# processor.net
KiCad netlist of a schematic drawn in Altium Designer
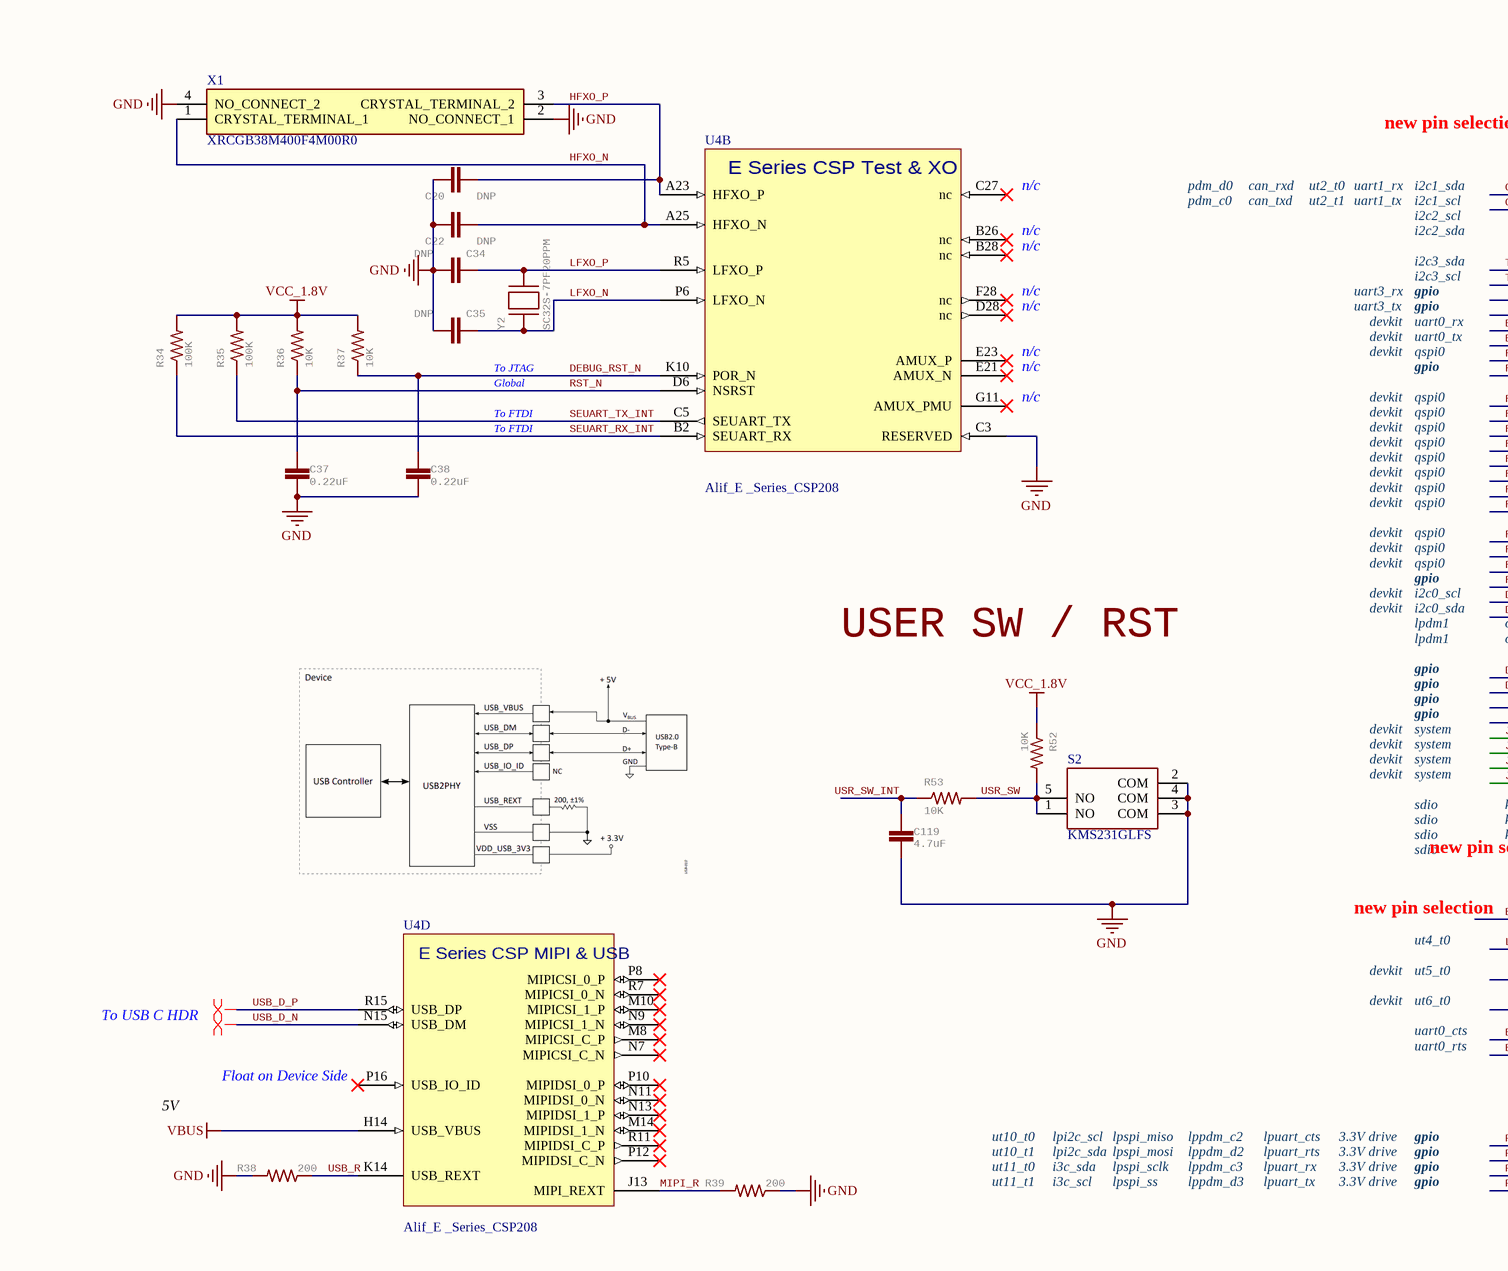
[diagram p0: processor.SchDoc, top left]
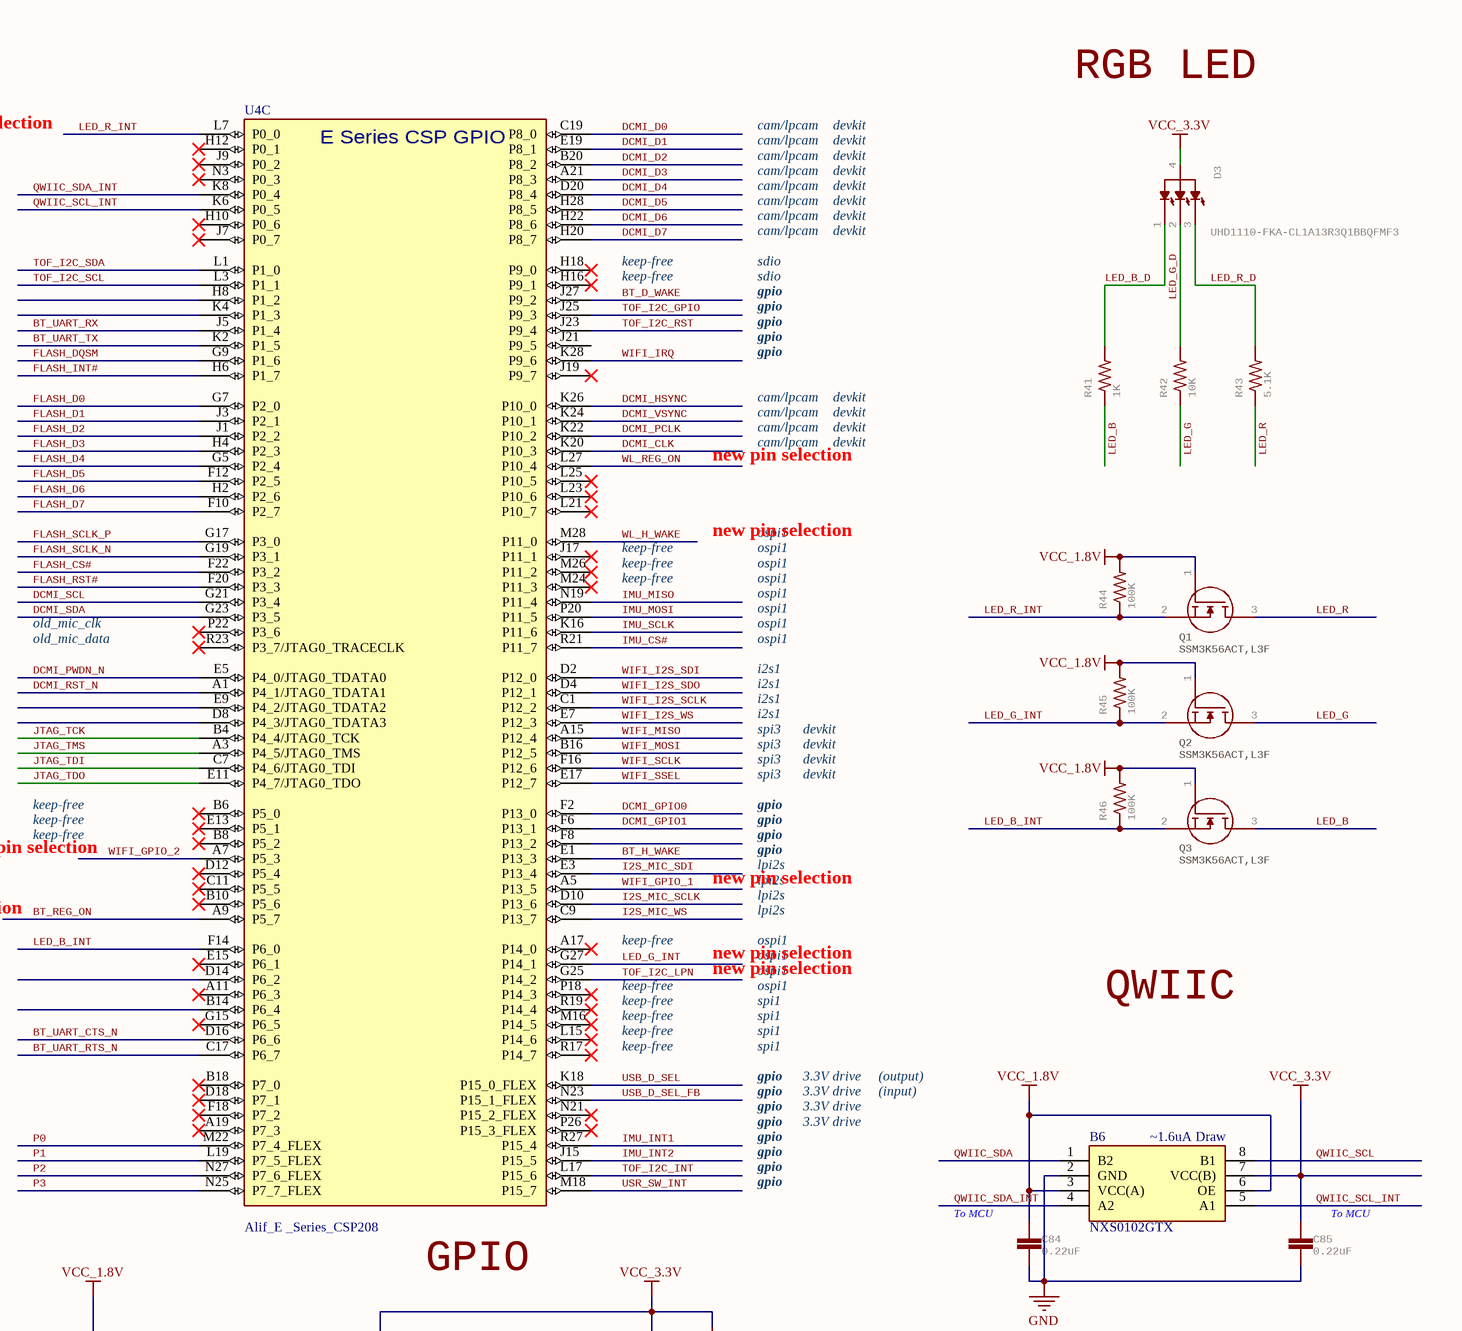
[diagram p1: processor.SchDoc, top right]
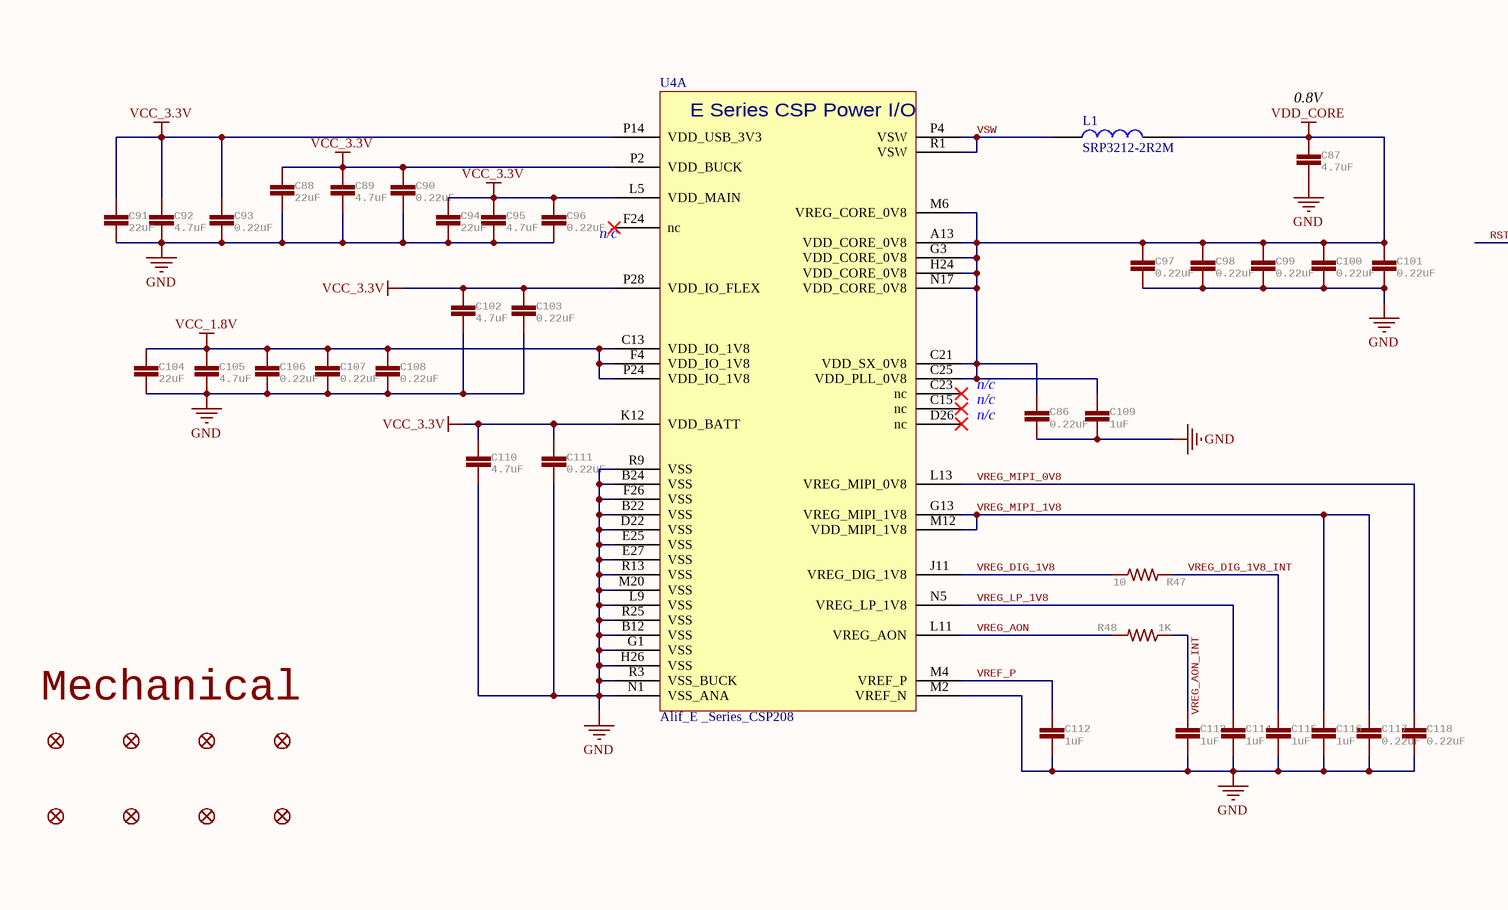
[diagram p2: processor.SchDoc, bottom left]
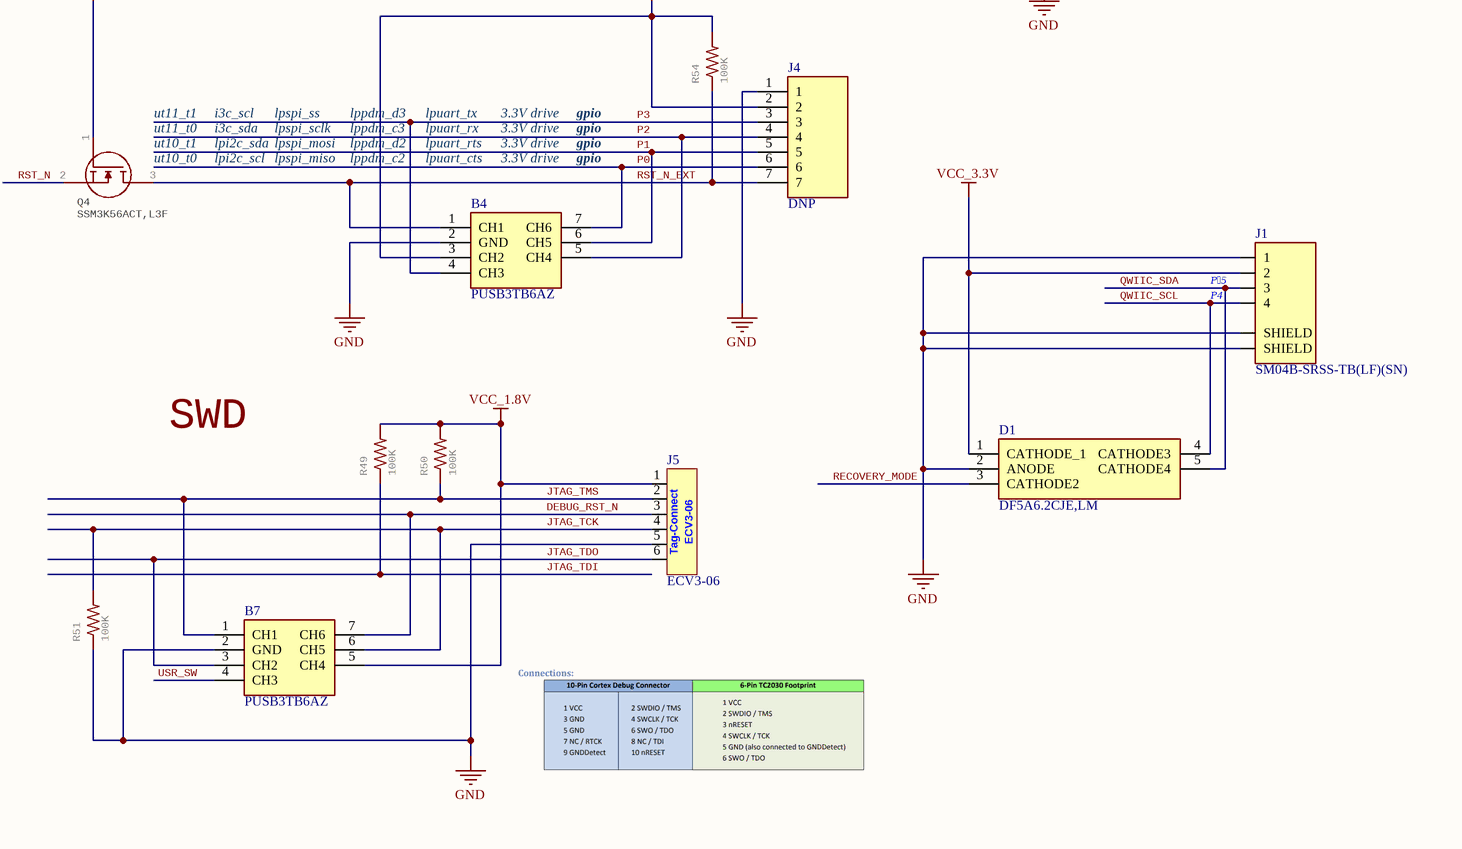
[diagram p3: processor.SchDoc, bottom right]

(export (version "E")
  (design (tool "Eeschema 10.0.6"))
  (components
    (comp (ref "B4")
      (value "PUSB3TB6AZ")
      (footprint "PUSB3TB6AZ")
      (description "NEXPERIA - PUSB3TB6AZ - DIODE, ESD PROTECTION, 5.5V, 0.27PF")
      (fields (field (name "MOUSER PART NUMBER") "771-PUSB3TB6AZ"))
      (libsource (lib "openmv-ae3") (part "PUSB3TB6AZ"))
    )
    (comp (ref "B6")
      (value "NXS0102GTX")
      (footprint "NXS0102GTX")
      (description "Dual supply translating transceiver; open drain; auto direction sensing")
      (fields (field (name "MOUSER PART NUMBER") "771-NXS0102GTX"))
      (libsource (lib "openmv-ae3") (part "NXS0102GTX"))
    )
    (comp (ref "B7")
      (value "PUSB3TB6AZ")
      (footprint "PUSB3TB6AZ")
      (description "NEXPERIA - PUSB3TB6AZ - DIODE, ESD PROTECTION, 5.5V, 0.27PF")
      (fields (field (name "MOUSER PART NUMBER") "771-PUSB3TB6AZ"))
      (libsource (lib "openmv-ae3") (part "PUSB3TB6AZ"))
    )
    (comp (ref "C20")
      (value "DNP")
      (footprint "C0201")
      (description "CAPACITOR, European symbol")
      (libsource (lib "") (part "C-EUC0201_3"))
    )
    (comp (ref "C22")
      (value "DNP")
      (footprint "C0201")
      (description "CAPACITOR, European symbol")
      (libsource (lib "") (part "C-EUC0201_3"))
    )
    (comp (ref "C34")
      (value "DNP")
      (footprint "C0201")
      (description "CAPACITOR, European symbol")
      (libsource (lib "") (part "C-EUC0201_2"))
    )
    (comp (ref "C35")
      (value "DNP")
      (footprint "C0201")
      (description "CAPACITOR, European symbol")
      (libsource (lib "") (part "C-EUC0201_2"))
    )
    (comp (ref "C37")
      (value "0.22uF")
      (footprint "C0201")
      (description "CAPACITOR, European symbol")
      (fields (field (name "MPN") "GRM033R60J224ME15D"))
      (libsource (lib "openmv-ae3") (part "C-EUC0201"))
    )
    (comp (ref "C38")
      (value "0.22uF")
      (footprint "C0201")
      (description "CAPACITOR, European symbol")
      (fields (field (name "MPN") "GRM033R60J224ME15D"))
      (libsource (lib "openmv-ae3") (part "C-EUC0201"))
    )
    (comp (ref "C84")
      (value "0.22uF")
      (footprint "C0201")
      (description "CAPACITOR, European symbol")
      (fields (field (name "MPN") "GRM033R60J224ME15D"))
      (libsource (lib "openmv-ae3") (part "C-EUC0201"))
    )
    (comp (ref "C85")
      (value "0.22uF")
      (footprint "C0201")
      (description "CAPACITOR, European symbol")
      (fields (field (name "MPN") "GRM033R60J224ME15D"))
      (libsource (lib "openmv-ae3") (part "C-EUC0201"))
    )
    (comp (ref "C86")
      (value "0.22uF")
      (footprint "C0201")
      (description "CAPACITOR, European symbol")
      (fields (field (name "MPN") "GRM033R60J224ME15D"))
      (libsource (lib "") (part "C-EUC0201_1"))
    )
    (comp (ref "C87")
      (value "4.7uF")
      (footprint "0402-CAP")
      (description "CapacitorStandard 0603 ceramic capacitor, and 0.1\" leaded capacitor.")
      (fields (field (name "MPN") "JMK105BBJ475MV-F") (field (name "LIBRARYNAME") "sfe"))
      (libsource (lib "openmv-ae3") (part "CAP0402-CAP"))
    )
    (comp (ref "C88")
      (value "22uF")
      (footprint "0805")
      (fields (field (name "MPN") "CL21A226MQQNNNE"))
      (libsource (lib "openmv-ae3") (part "22UF-0805-6.3V-20%"))
    )
    (comp (ref "C89")
      (value "4.7uF")
      (footprint "0402-CAP")
      (description "CapacitorStandard 0603 ceramic capacitor, and 0.1\" leaded capacitor.")
      (fields (field (name "MPN") "JMK105BBJ475MV-F") (field (name "LIBRARYNAME") "sfe"))
      (libsource (lib "openmv-ae3") (part "CAP0402-CAP"))
    )
    (comp (ref "C90")
      (value "0.22uF")
      (footprint "C0201")
      (description "CAPACITOR, European symbol")
      (fields (field (name "MPN") "GRM033R60J224ME15D"))
      (libsource (lib "openmv-ae3") (part "C-EUC0201"))
    )
    (comp (ref "C91")
      (value "22uF")
      (footprint "0805")
      (fields (field (name "MPN") "CL21A226MQQNNNE"))
      (libsource (lib "openmv-ae3") (part "22UF-0805-6.3V-20%"))
    )
    (comp (ref "C92")
      (value "4.7uF")
      (footprint "0402-CAP")
      (description "CapacitorStandard 0603 ceramic capacitor, and 0.1\" leaded capacitor.")
      (fields (field (name "MPN") "JMK105BBJ475MV-F") (field (name "LIBRARYNAME") "sfe"))
      (libsource (lib "openmv-ae3") (part "CAP0402-CAP"))
    )
    (comp (ref "C93")
      (value "0.22uF")
      (footprint "C0201")
      (description "CAPACITOR, European symbol")
      (fields (field (name "MPN") "GRM033R60J224ME15D"))
      (libsource (lib "openmv-ae3") (part "C-EUC0201"))
    )
    (comp (ref "C94")
      (value "22uF")
      (footprint "0805")
      (fields (field (name "MPN") "CL21A226MQQNNNE"))
      (libsource (lib "openmv-ae3") (part "22UF-0805-6.3V-20%"))
    )
    (comp (ref "C95")
      (value "4.7uF")
      (footprint "0402-CAP")
      (description "CapacitorStandard 0603 ceramic capacitor, and 0.1\" leaded capacitor.")
      (fields (field (name "MPN") "JMK105BBJ475MV-F") (field (name "LIBRARYNAME") "sfe"))
      (libsource (lib "openmv-ae3") (part "CAP0402-CAP"))
    )
    (comp (ref "C96")
      (value "0.22uF")
      (footprint "C0201")
      (description "CAPACITOR, European symbol")
      (fields (field (name "MPN") "GRM033R60J224ME15D"))
      (libsource (lib "openmv-ae3") (part "C-EUC0201"))
    )
    (comp (ref "C97")
      (value "0.22uF")
      (footprint "C0201")
      (description "CAPACITOR, European symbol")
      (fields (field (name "MPN") "GRM033R60J224ME15D"))
      (libsource (lib "openmv-ae3") (part "C-EUC0201"))
    )
    (comp (ref "C98")
      (value "0.22uF")
      (footprint "C0201")
      (description "CAPACITOR, European symbol")
      (fields (field (name "MPN") "GRM033R60J224ME15D"))
      (libsource (lib "openmv-ae3") (part "C-EUC0201"))
    )
    (comp (ref "C99")
      (value "0.22uF")
      (footprint "C0201")
      (description "CAPACITOR, European symbol")
      (fields (field (name "MPN") "GRM033R60J224ME15D"))
      (libsource (lib "openmv-ae3") (part "C-EUC0201"))
    )
    (comp (ref "C100")
      (value "0.22uF")
      (footprint "C0201")
      (description "CAPACITOR, European symbol")
      (fields (field (name "MPN") "GRM033R60J224ME15D"))
      (libsource (lib "openmv-ae3") (part "C-EUC0201"))
    )
    (comp (ref "C101")
      (value "0.22uF")
      (footprint "C0201")
      (description "CAPACITOR, European symbol")
      (fields (field (name "MPN") "GRM033R60J224ME15D"))
      (libsource (lib "openmv-ae3") (part "C-EUC0201"))
    )
    (comp (ref "C102")
      (value "4.7uF")
      (footprint "0402-CAP")
      (description "CapacitorStandard 0603 ceramic capacitor, and 0.1\" leaded capacitor.")
      (fields (field (name "MPN") "JMK105BBJ475MV-F") (field (name "LIBRARYNAME") "sfe"))
      (libsource (lib "openmv-ae3") (part "CAP0402-CAP"))
    )
    (comp (ref "C103")
      (value "0.22uF")
      (footprint "C0201")
      (description "CAPACITOR, European symbol")
      (fields (field (name "MPN") "GRM033R60J224ME15D"))
      (libsource (lib "openmv-ae3") (part "C-EUC0201"))
    )
    (comp (ref "C104")
      (value "22uF")
      (footprint "0805")
      (fields (field (name "MPN") "CL21A226MQQNNNE"))
      (libsource (lib "openmv-ae3") (part "22UF-0805-6.3V-20%"))
    )
    (comp (ref "C105")
      (value "4.7uF")
      (footprint "0402-CAP")
      (description "CapacitorStandard 0603 ceramic capacitor, and 0.1\" leaded capacitor.")
      (fields (field (name "MPN") "JMK105BBJ475MV-F") (field (name "LIBRARYNAME") "sfe"))
      (libsource (lib "openmv-ae3") (part "CAP0402-CAP"))
    )
    (comp (ref "C106")
      (value "0.22uF")
      (footprint "C0201")
      (description "CAPACITOR, European symbol")
      (fields (field (name "MPN") "GRM033R60J224ME15D"))
      (libsource (lib "openmv-ae3") (part "C-EUC0201"))
    )
    (comp (ref "C107")
      (value "0.22uF")
      (footprint "C0201")
      (description "CAPACITOR, European symbol")
      (fields (field (name "MPN") "GRM033R60J224ME15D"))
      (libsource (lib "openmv-ae3") (part "C-EUC0201"))
    )
    (comp (ref "C108")
      (value "0.22uF")
      (footprint "C0201")
      (description "CAPACITOR, European symbol")
      (fields (field (name "MPN") "GRM033R60J224ME15D"))
      (libsource (lib "openmv-ae3") (part "C-EUC0201"))
    )
    (comp (ref "C109")
      (value "1uF")
      (footprint "C0201")
      (description "CAPACITOR, European symbol")
      (fields (field (name "MPN") "CL03A105MQ3CSNC"))
      (libsource (lib "") (part "C-EUC0201_1"))
    )
    (comp (ref "C110")
      (value "4.7uF")
      (footprint "0402-CAP")
      (description "CapacitorStandard 0603 ceramic capacitor, and 0.1\" leaded capacitor.")
      (fields (field (name "MPN") "JMK105BBJ475MV-F") (field (name "LIBRARYNAME") "sfe"))
      (libsource (lib "openmv-ae3") (part "CAP0402-CAP"))
    )
    (comp (ref "C111")
      (value "0.22uF")
      (footprint "C0201")
      (description "CAPACITOR, European symbol")
      (fields (field (name "MPN") "GRM033R60J224ME15D"))
      (libsource (lib "openmv-ae3") (part "C-EUC0201"))
    )
    (comp (ref "C112")
      (value "1uF")
      (footprint "C0201")
      (description "CAPACITOR, European symbol")
      (fields (field (name "MPN") "CL03A105MQ3CSNC"))
      (libsource (lib "openmv-ae3") (part "C-EUC0201"))
    )
    (comp (ref "C113")
      (value "1uF")
      (footprint "C0201")
      (description "CAPACITOR, European symbol")
      (fields (field (name "MPN") "CL03A105MQ3CSNC"))
      (libsource (lib "openmv-ae3") (part "C-EUC0201"))
    )
    (comp (ref "C114")
      (value "1uF")
      (footprint "C0201")
      (description "CAPACITOR, European symbol")
      (fields (field (name "MPN") "CL03A105MQ3CSNC"))
      (libsource (lib "openmv-ae3") (part "C-EUC0201"))
    )
    (comp (ref "C115")
      (value "1uF")
      (footprint "C0201")
      (description "CAPACITOR, European symbol")
      (fields (field (name "MPN") "CL03A105MQ3CSNC"))
      (libsource (lib "openmv-ae3") (part "C-EUC0201"))
    )
    (comp (ref "C116")
      (value "1uF")
      (footprint "C0201")
      (description "CAPACITOR, European symbol")
      (fields (field (name "MPN") "CL03A105MQ3CSNC"))
      (libsource (lib "openmv-ae3") (part "C-EUC0201"))
    )
    (comp (ref "C117")
      (value "0.22uF")
      (footprint "C0201")
      (description "CAPACITOR, European symbol")
      (fields (field (name "MPN") "GRM033R60J224ME15D"))
      (libsource (lib "openmv-ae3") (part "C-EUC0201"))
    )
    (comp (ref "C118")
      (value "0.22uF")
      (footprint "C0201")
      (description "CAPACITOR, European symbol")
      (fields (field (name "MPN") "GRM033R60J224ME15D"))
      (libsource (lib "openmv-ae3") (part "C-EUC0201"))
    )
    (comp (ref "C119")
      (value "4.7uF")
      (footprint "0402-CAP")
      (description "CapacitorStandard 0603 ceramic capacitor, and 0.1\" leaded capacitor.")
      (fields (field (name "MPN") "JMK105BBJ475MV-F") (field (name "LIBRARYNAME") "sfe"))
      (libsource (lib "openmv-ae3") (part "CAP0402-CAP"))
    )
    (comp (ref "D1")
      (value "DF5A6.2CJE,LM")
      (footprint "SamacSys:SOTFL50P160X60-5N")
      (description "Diode")
      (fields (field (name "MOUSER PART NUMBER") "757-DF5A6.2CJE,LM"))
      (libsource (lib "openmv-ae3") (part "DF5A5.6CJE,LM"))
    )
    (comp (ref "D3")
      (value "UHD1110-FKA-CL1A13R3Q1BBQFMF3")
      (footprint "LED_UHD1110-FKA-CL1A13R3Q1BBQFMF3")
      (description "LED RGB SMD, SIZE 1 X 1 mm Check availability")
      (fields (field (name "MF") "Cree Inc.") (field (name "MPN") "UHD1110-FKA-CL1A13r3q1BBQFMF3"))
      (libsource (lib "openmv-ae3") (part "UHD1110-FKA-CL1A13R3Q1BBQFMF3"))
    )
    (comp (ref "FD1")
      (value "FIDUCIAL1X2")
      (footprint "FIDUCIAL-1X2")
      (fields (field (name "LIBRARYNAME") "SparkFun-Aesthetics"))
      (libsource (lib "openmv-ae3") (part "FIDUCIAL1X2"))
    )
    (comp (ref "FD2")
      (value "FIDUCIAL1X2")
      (footprint "FIDUCIAL-1X2")
      (fields (field (name "LIBRARYNAME") "SparkFun-Aesthetics"))
      (libsource (lib "openmv-ae3") (part "FIDUCIAL1X2"))
    )
    (comp (ref "FD3")
      (value "FIDUCIAL1X2")
      (footprint "FIDUCIAL-1X2")
      (fields (field (name "LIBRARYNAME") "SparkFun-Aesthetics"))
      (libsource (lib "openmv-ae3") (part "FIDUCIAL1X2"))
    )
    (comp (ref "FD4")
      (value "FIDUCIAL1X2")
      (footprint "FIDUCIAL-1X2")
      (fields (field (name "LIBRARYNAME") "SparkFun-Aesthetics"))
      (libsource (lib "openmv-ae3") (part "FIDUCIAL1X2"))
    )
    (comp (ref "FD5")
      (value "FIDUCIAL1X2")
      (footprint "FIDUCIAL-1X2")
      (fields (field (name "LIBRARYNAME") "SparkFun-Aesthetics"))
      (libsource (lib "openmv-ae3") (part "FIDUCIAL1X2"))
    )
    (comp (ref "FD6")
      (value "FIDUCIAL1X2")
      (footprint "FIDUCIAL-1X2")
      (fields (field (name "LIBRARYNAME") "SparkFun-Aesthetics"))
      (libsource (lib "openmv-ae3") (part "FIDUCIAL1X2"))
    )
    (comp (ref "FD7")
      (value "FIDUCIAL1X2")
      (footprint "FIDUCIAL-1X2")
      (fields (field (name "LIBRARYNAME") "SparkFun-Aesthetics"))
      (libsource (lib "openmv-ae3") (part "FIDUCIAL1X2"))
    )
    (comp (ref "FD8")
      (value "FIDUCIAL1X2")
      (footprint "FIDUCIAL-1X2")
      (fields (field (name "LIBRARYNAME") "SparkFun-Aesthetics"))
      (libsource (lib "openmv-ae3") (part "FIDUCIAL1X2"))
    )
    (comp (ref "J1")
      (value "SM04B-SRSS-TB(LF)(SN)")
      (footprint "JST_SM04B-SRSS-TB(LF)(SN)")
      (description "SH Series 1.0 mm Pitch 2 Position Single Row Side Entry Shrouded Header")
      (libsource (lib "openmv-ae3") (part "SM04B-SRSS-TB(LF)(SN)"))
    )
    (comp (ref "J4")
      (value "DNP")
      (footprint "SamacSys:HDRV7W66P0X254_1X7_1778X254X844P")
      (description "Connector")
      (fields
        (field (name "MANUFACTURER_PART_NUMBER") "M20-9770746")
        (field (name "MOUSER PART NUMBER") "855-M20-9770746")
      )
      (libsource (lib "openmv-ae3") (part "M20-9770746"))
    )
    (comp (ref "J5")
      (value "ECV3-06")
      (footprint "Tag-Connect-ECV3-Footprints:ECV3-06")
      (description "Tag-Connect Edge-Connect ECV3-06 No-Solder Debug Castellated Pads Connector DO NOT PLACE NO BOM")
      (libsource (lib "openmv-ae3") (part "ECV3-06"))
    )
    (comp (ref "L1")
      (value "SRP3212-2R2M")
      (footprint "IND3225X100N")
      (description "Ind,3.2x2.5x1mm,2.2uH?20%,4A,shd")
      (fields (field (name "MOUSER PART NUMBER") "652-SRP3212-2R2M"))
      (libsource (lib "openmv-ae3") (part "SRP3212-2R2M"))
    )
    (comp (ref "Q1")
      (value "NMOS")
      (footprint "DFN1006")
      (fields (field (name "MPN") "SSM3K56ACT,L3F") (field (name "PART NUMBER") "SSM3K56ACT,L3F"))
      (libsource (lib "openmv-ae3") (part "NMOS"))
    )
    (comp (ref "Q2")
      (value "NMOS")
      (footprint "DFN1006")
      (fields (field (name "MPN") "SSM3K56ACT,L3F") (field (name "PART NUMBER") "SSM3K56ACT,L3F"))
      (libsource (lib "openmv-ae3") (part "NMOS"))
    )
    (comp (ref "Q3")
      (value "NMOS")
      (footprint "DFN1006")
      (fields (field (name "MPN") "SSM3K56ACT,L3F") (field (name "PART NUMBER") "SSM3K56ACT,L3F"))
      (libsource (lib "openmv-ae3") (part "NMOS"))
    )
    (comp (ref "Q4")
      (value "NMOS")
      (footprint "DFN1006")
      (fields (field (name "MPN") "SSM3K56ACT,L3F") (field (name "PART NUMBER") "SSM3K56ACT,L3F"))
      (libsource (lib "openmv-ae3") (part "NMOS"))
    )
    (comp (ref "R34")
      (value "100K")
      (footprint "R0201")
      (fields (field (name "MPN") "RMCF0201FT100K") (field (name "LIBRARYNAME") "sfe"))
      (libsource (lib "openmv-ae3") (part "RESISTOR0402-RES"))
    )
    (comp (ref "R35")
      (value "100K")
      (footprint "R0201")
      (fields (field (name "MPN") "RMCF0201FT100K") (field (name "LIBRARYNAME") "sfe"))
      (libsource (lib "openmv-ae3") (part "RESISTOR0402-RES"))
    )
    (comp (ref "R36")
      (value "10K")
      (footprint "R0201")
      (fields (field (name "MPN") "RMCF0201FT10K0") (field (name "LIBRARYNAME") "sfe"))
      (libsource (lib "openmv-ae3") (part "RESISTOR0402-RES"))
    )
    (comp (ref "R37")
      (value "10K")
      (footprint "R0201")
      (fields (field (name "MPN") "RMCF0201FT10K0") (field (name "LIBRARYNAME") "sfe"))
      (libsource (lib "openmv-ae3") (part "RESISTOR0402-RES"))
    )
    (comp (ref "R38")
      (value "200")
      (footprint "R0201")
      (fields (field (name "MPN") "CR0201-FW-2000GLF") (field (name "LIBRARYNAME") "sfe"))
      (libsource (lib "openmv-ae3") (part "RESISTOR0402-RES"))
    )
    (comp (ref "R39")
      (value "200")
      (footprint "R0201")
      (fields (field (name "MPN") "CR0201-FW-2000GLF") (field (name "LIBRARYNAME") "sfe"))
      (libsource (lib "openmv-ae3") (part "RESISTOR0402-RES"))
    )
    (comp (ref "R41")
      (value "1K")
      (footprint "R0201")
      (description "ResistorBasic schematic elements and footprints for 0603, 1206, and PTH resistors.")
      (fields (field (name "MPN") "RMCF0201FT1K00") (field (name "LIBRARYNAME") "sfe"))
      (libsource (lib "openmv-ae3") (part "RESISTOR0402-RES"))
    )
    (comp (ref "R42")
      (value "10K")
      (footprint "R0201")
      (description "ResistorBasic schematic elements and footprints for 0603, 1206, and PTH resistors.")
      (fields (field (name "MPN") "RMCF0201FT10K0") (field (name "LIBRARYNAME") "sfe"))
      (libsource (lib "openmv-ae3") (part "RESISTOR0402-RES"))
    )
    (comp (ref "R43")
      (value "5.1K")
      (footprint "R0201")
      (description "ResistorBasic schematic elements and footprints for 0603, 1206, and PTH resistors.")
      (fields (field (name "MPN") "AC0201FR-075K1L") (field (name "LIBRARYNAME") "sfe"))
      (libsource (lib "openmv-ae3") (part "RESISTOR0402-RES"))
    )
    (comp (ref "R44")
      (value "100K")
      (footprint "R0201")
      (fields (field (name "MPN") "RMCF0201FT100K") (field (name "LIBRARYNAME") "sfe"))
      (libsource (lib "openmv-ae3") (part "RESISTOR0402-RES"))
    )
    (comp (ref "R45")
      (value "100K")
      (footprint "R0201")
      (fields (field (name "MPN") "RMCF0201FT100K") (field (name "LIBRARYNAME") "sfe"))
      (libsource (lib "openmv-ae3") (part "RESISTOR0402-RES"))
    )
    (comp (ref "R46")
      (value "100K")
      (footprint "R0201")
      (fields (field (name "MPN") "RMCF0201FT100K") (field (name "LIBRARYNAME") "sfe"))
      (libsource (lib "openmv-ae3") (part "RESISTOR0402-RES"))
    )
    (comp (ref "R47")
      (value "10")
      (footprint "R0201")
      (fields (field (name "MPN") "RMCF0201JT10R0") (field (name "LIBRARYNAME") "sfe"))
      (libsource (lib "openmv-ae3") (part "RESISTOR0402-RES"))
    )
    (comp (ref "R48")
      (value "1K")
      (footprint "R0201")
      (fields (field (name "MPN") "RMCF0201FT1K00") (field (name "LIBRARYNAME") "sfe"))
      (libsource (lib "openmv-ae3") (part "RESISTOR0402-RES"))
    )
    (comp (ref "R49")
      (value "100K")
      (footprint "R0201")
      (fields (field (name "MPN") "RMCF0201FT100K") (field (name "LIBRARYNAME") "sfe"))
      (libsource (lib "openmv-ae3") (part "RESISTOR0402-RES"))
    )
    (comp (ref "R50")
      (value "100K")
      (footprint "R0201")
      (fields (field (name "MPN") "RMCF0201FT100K") (field (name "LIBRARYNAME") "sfe"))
      (libsource (lib "openmv-ae3") (part "RESISTOR0402-RES"))
    )
    (comp (ref "R51")
      (value "100K")
      (footprint "R0201")
      (fields (field (name "MPN") "RMCF0201FT100K") (field (name "LIBRARYNAME") "sfe"))
      (libsource (lib "openmv-ae3") (part "RESISTOR0402-RES"))
    )
    (comp (ref "R52")
      (value "10K")
      (footprint "R0201")
      (fields (field (name "MPN") "RMCF0201FT10K0") (field (name "LIBRARYNAME") "sfe"))
      (libsource (lib "openmv-ae3") (part "RESISTOR0402-RES"))
    )
    (comp (ref "R53")
      (value "10K")
      (footprint "R0201")
      (fields (field (name "MPN") "RMCF0201FT10K0") (field (name "LIBRARYNAME") "sfe"))
      (libsource (lib "openmv-ae3") (part "RESISTOR0402-RES"))
    )
    (comp (ref "R54")
      (value "100K")
      (footprint "R0201")
      (fields (field (name "MPN") "RMCF0201FT100K") (field (name "LIBRARYNAME") "sfe"))
      (libsource (lib "openmv-ae3") (part "RESISTOR0402-RES"))
    )
    (comp (ref "S2")
      (value "KMS231GLFS")
      (footprint "KMS231GLFS")
      (libsource (lib "openmv-ae3") (part "KMS231GLFS"))
    )
    (comp (ref "U4")
      (value "Alif_E _Series_CSP208")
      (footprint "CSP208")
      (description "IC,Alif E7 MCU, Rev B silicon,CSP208")
      (fields (field (name "MPN") "AE302F80F55D5AE"))
      (libsource (lib "openmv-ae3") (part "E7_B0_CSP_208"))
    )
    (comp (ref "X1")
      (value "XRCGB38M400F4M00R0")
      (footprint "XTAL_2016")
      (description "2.0X1.6X0.65MM 38.4MHZ CRYSTAL")
      (libsource (lib "openmv-ae3") (part "XRCGB38M400F4M00R0"))
    )
    (comp (ref "Y2")
      (value "SC32S-7PF20PPM")
      (footprint "XTAL_ABS07-32.768KHZ-7-T")
      (description "Check availability")
      (fields (field (name "MF") "Abracon") (field (name "MP") "ABS07-32.768KHZ-7-T"))
      (libsource (lib "openmv-ae3") (part "ABS07-32.768KHZ-7-T"))
    )
  )
  (nets
    (net (code "1") (name "/BT_D_WAKE") (class "Default")
      (node (ref "U4") (pin "J27") (pinfunction "P9_2_J27") (pintype "bidirectional"))
    )
    (net (code "2") (name "/BT_H_WAKE") (class "Default")
      (node (ref "U4") (pin "E1") (pinfunction "P13_3_E1") (pintype "bidirectional"))
    )
    (net (code "3") (name "/BT_REG_ON") (class "Default")
      (node (ref "U4") (pin "A9") (pinfunction "P5_7_A9") (pintype "bidirectional"))
    )
    (net (code "4") (name "/BT_UART_CTS_N") (class "Default")
      (node (ref "U4") (pin "D16") (pinfunction "P6_6_D16") (pintype "bidirectional"))
    )
    (net (code "5") (name "/BT_UART_RTS_N") (class "Default")
      (node (ref "U4") (pin "C17") (pinfunction "P6_7_C17") (pintype "bidirectional"))
    )
    (net (code "6") (name "/BT_UART_RX") (class "Default")
      (node (ref "U4") (pin "J5") (pinfunction "P1_4_J5") (pintype "bidirectional"))
    )
    (net (code "7") (name "/BT_UART_TX") (class "Default")
      (node (ref "U4") (pin "K2") (pinfunction "P1_5_K2") (pintype "bidirectional"))
    )
    (net (code "8") (name "/DCMI_CLK") (class "Default")
      (node (ref "U4") (pin "K20") (pinfunction "P10_3_K20") (pintype "bidirectional"))
    )
    (net (code "9") (name "/DCMI_D0") (class "Default")
      (node (ref "U4") (pin "C19") (pinfunction "P8_0_C19") (pintype "bidirectional"))
    )
    (net (code "10") (name "/DCMI_D1") (class "Default")
      (node (ref "U4") (pin "E19") (pinfunction "P8_1_E19") (pintype "bidirectional"))
    )
    (net (code "11") (name "/DCMI_D2") (class "Default")
      (node (ref "U4") (pin "B20") (pinfunction "P8_2_B20") (pintype "bidirectional"))
    )
    (net (code "12") (name "/DCMI_D3") (class "Default")
      (node (ref "U4") (pin "A21") (pinfunction "P8_3_A21") (pintype "bidirectional"))
    )
    (net (code "13") (name "/DCMI_D4") (class "Default")
      (node (ref "U4") (pin "D20") (pinfunction "P8_4_D20") (pintype "bidirectional"))
    )
    (net (code "14") (name "/DCMI_D5") (class "Default")
      (node (ref "U4") (pin "H28") (pinfunction "P8_5_H28") (pintype "bidirectional"))
    )
    (net (code "15") (name "/DCMI_D6") (class "Default")
      (node (ref "U4") (pin "H22") (pinfunction "P8_6_H22") (pintype "bidirectional"))
    )
    (net (code "16") (name "/DCMI_D7") (class "Default")
      (node (ref "U4") (pin "H20") (pinfunction "P8_7_H20") (pintype "bidirectional"))
    )
    (net (code "17") (name "/DCMI_GPIO0") (class "Default")
      (node (ref "U4") (pin "F2") (pinfunction "P13_0_F2") (pintype "bidirectional"))
    )
    (net (code "18") (name "/DCMI_GPIO1") (class "Default")
      (node (ref "U4") (pin "F6") (pinfunction "P13_1_F6") (pintype "bidirectional"))
    )
    (net (code "19") (name "/DCMI_HSYNC") (class "Default")
      (node (ref "U4") (pin "K26") (pinfunction "P10_0_K26") (pintype "bidirectional"))
    )
    (net (code "20") (name "/DCMI_PCLK") (class "Default")
      (node (ref "U4") (pin "K22") (pinfunction "P10_2_K22") (pintype "bidirectional"))
    )
    (net (code "21") (name "/DCMI_PWDN_N") (class "Default")
      (node (ref "U4") (pin "E5") (pinfunction "P4_0/JTAG0_TDATA0_E5") (pintype "bidirectional"))
    )
    (net (code "22") (name "/DCMI_RST_N") (class "Default")
      (node (ref "U4") (pin "A1") (pinfunction "P4_1/JTAG0_TDATA1_A1") (pintype "bidirectional"))
    )
    (net (code "23") (name "/DCMI_SCL") (class "Default")
      (node (ref "U4") (pin "G21") (pinfunction "P3_4_G21") (pintype "bidirectional"))
    )
    (net (code "24") (name "/DCMI_SDA") (class "Default")
      (node (ref "U4") (pin "G23") (pinfunction "P3_5_G23") (pintype "bidirectional"))
    )
    (net (code "25") (name "/DCMI_VSYNC") (class "Default")
      (node (ref "U4") (pin "K24") (pinfunction "P10_1_K24") (pintype "bidirectional"))
    )
    (net (code "26") (name "/DEBUG_RST_N") (class "Default")
      (node (ref "B7") (pin "7") (pinfunction "CH6_7") (pintype "passive"))
      (node (ref "C38") (pin "2") (pinfunction "2_2") (pintype "passive"))
      (node (ref "J5") (pin "3") (pintype "passive"))
      (node (ref "R37") (pin "1") (pinfunction "1_1") (pintype "passive"))
      (node (ref "U4") (pin "K10") (pinfunction "POR_N_K10") (pintype "input"))
    )
    (net (code "27") (name "/FLASH_CS#") (class "Default")
      (node (ref "U4") (pin "F22") (pinfunction "P3_2_F22") (pintype "bidirectional"))
    )
    (net (code "28") (name "/FLASH_D0") (class "Default")
      (node (ref "U4") (pin "G7") (pinfunction "P2_0_G7") (pintype "bidirectional"))
    )
    (net (code "29") (name "/FLASH_D1") (class "Default")
      (node (ref "U4") (pin "J3") (pinfunction "P2_1_J3") (pintype "bidirectional"))
    )
    (net (code "30") (name "/FLASH_D2") (class "Default")
      (node (ref "U4") (pin "J1") (pinfunction "P2_2_J1") (pintype "bidirectional"))
    )
    (net (code "31") (name "/FLASH_D3") (class "Default")
      (node (ref "U4") (pin "H4") (pinfunction "P2_3_H4") (pintype "bidirectional"))
    )
    (net (code "32") (name "/FLASH_D4") (class "Default")
      (node (ref "U4") (pin "G5") (pinfunction "P2_4_G5") (pintype "bidirectional"))
    )
    (net (code "33") (name "/FLASH_D5") (class "Default")
      (node (ref "U4") (pin "F12") (pinfunction "P2_5_F12") (pintype "bidirectional"))
    )
    (net (code "34") (name "/FLASH_D6") (class "Default")
      (node (ref "U4") (pin "H2") (pinfunction "P2_6_H2") (pintype "bidirectional"))
    )
    (net (code "35") (name "/FLASH_D7") (class "Default")
      (node (ref "U4") (pin "F10") (pinfunction "P2_7_F10") (pintype "bidirectional"))
    )
    (net (code "36") (name "/FLASH_DQSM") (class "Default")
      (node (ref "U4") (pin "G9") (pinfunction "P1_6_G9") (pintype "bidirectional"))
    )
    (net (code "37") (name "/FLASH_INT#") (class "Default")
      (node (ref "U4") (pin "H6") (pinfunction "P1_7_H6") (pintype "bidirectional"))
    )
    (net (code "38") (name "/FLASH_RST#") (class "Default")
      (node (ref "U4") (pin "F20") (pinfunction "P3_3_F20") (pintype "bidirectional"))
    )
    (net (code "39") (name "/FLASH_SCLK_N") (class "Default")
      (node (ref "U4") (pin "G19") (pinfunction "P3_1_G19") (pintype "bidirectional"))
    )
    (net (code "40") (name "/FLASH_SCLK_P") (class "Default")
      (node (ref "U4") (pin "G17") (pinfunction "P3_0_G17") (pintype "bidirectional"))
    )
    (net (code "41") (name "/HFXO_N") (class "Default")
      (node (ref "C22") (pin "2") (pinfunction "2_2") (pintype "passive"))
      (node (ref "U4") (pin "A25") (pinfunction "HFXO_N_A25") (pintype "input"))
      (node (ref "X1") (pin "1") (pinfunction "CRYSTAL_TERMINAL_1_1") (pintype "passive"))
    )
    (net (code "42") (name "/HFXO_P") (class "Default")
      (node (ref "C20") (pin "2") (pinfunction "2_2") (pintype "passive"))
      (node (ref "U4") (pin "A23") (pinfunction "HFXO_P_A23") (pintype "input"))
      (node (ref "X1") (pin "3") (pinfunction "CRYSTAL_TERMINAL_2_3") (pintype "passive"))
    )
    (net (code "43") (name "/I2S_MIC_SCLK") (class "Default")
      (node (ref "U4") (pin "D10") (pinfunction "P13_6_D10") (pintype "bidirectional"))
    )
    (net (code "44") (name "/I2S_MIC_SDI") (class "Default")
      (node (ref "U4") (pin "E3") (pinfunction "P13_4_E3") (pintype "bidirectional"))
    )
    (net (code "45") (name "/I2S_MIC_WS") (class "Default")
      (node (ref "U4") (pin "C9") (pinfunction "P13_7_C9") (pintype "bidirectional"))
    )
    (net (code "46") (name "/IMU_CS#") (class "Default")
      (node (ref "U4") (pin "R21") (pinfunction "P11_7_R21") (pintype "bidirectional"))
    )
    (net (code "47") (name "/IMU_INT1") (class "Default")
      (node (ref "U4") (pin "R27") (pinfunction "P15_4_R27") (pintype "bidirectional"))
    )
    (net (code "48") (name "/IMU_INT2") (class "Default")
      (node (ref "U4") (pin "J15") (pinfunction "P15_5_J15") (pintype "bidirectional"))
    )
    (net (code "49") (name "/IMU_MISO") (class "Default")
      (node (ref "U4") (pin "N19") (pinfunction "P11_4_N19") (pintype "bidirectional"))
    )
    (net (code "50") (name "/IMU_MOSI") (class "Default")
      (node (ref "U4") (pin "P20") (pinfunction "P11_5_P20") (pintype "bidirectional"))
    )
    (net (code "51") (name "/IMU_SCLK") (class "Default")
      (node (ref "U4") (pin "K16") (pinfunction "P11_6_K16") (pintype "bidirectional"))
    )
    (net (code "52") (name "/JTAG_TCK") (class "Default")
      (node (ref "B7") (pin "6") (pinfunction "CH5_6") (pintype "passive"))
      (node (ref "J5") (pin "4") (pintype "passive"))
      (node (ref "R51") (pin "2") (pinfunction "2_2") (pintype "passive"))
      (node (ref "U4") (pin "B4") (pinfunction "P4_4/JTAG0_TCK_B4") (pintype "bidirectional"))
    )
    (net (code "53") (name "/JTAG_TDI") (class "Default")
      (node (ref "R49") (pin "1") (pinfunction "1_1") (pintype "passive"))
      (node (ref "U4") (pin "C7") (pinfunction "P4_6/JTAG0_TDI_C7") (pintype "bidirectional"))
    )
    (net (code "54") (name "/JTAG_TDO") (class "Default")
      (node (ref "B7") (pin "3") (pinfunction "CH2_3") (pintype "passive"))
      (node (ref "J5") (pin "6") (pintype "passive"))
      (node (ref "U4") (pin "E11") (pinfunction "P4_7/JTAG0_TDO_E11") (pintype "bidirectional"))
    )
    (net (code "55") (name "/JTAG_TMS") (class "Default")
      (node (ref "B7") (pin "1") (pinfunction "CH1_1") (pintype "passive"))
      (node (ref "J5") (pin "2") (pintype "passive"))
      (node (ref "R50") (pin "1") (pinfunction "1_1") (pintype "passive"))
      (node (ref "U4") (pin "A3") (pinfunction "P4_5/JTAG0_TMS_A3") (pintype "bidirectional"))
    )
    (net (code "56") (name "/LED_B") (class "Default")
      (node (ref "Q3") (pin "3") (pinfunction "D_3") (pintype "bidirectional"))
      (node (ref "R41") (pin "1") (pinfunction "1_1") (pintype "passive"))
    )
    (net (code "57") (name "/LED_B_D") (class "Default")
      (node (ref "D3") (pin "1") (pinfunction "BLUE_1") (pintype "passive"))
      (node (ref "R41") (pin "2") (pinfunction "2_2") (pintype "passive"))
    )
    (net (code "58") (name "/LED_B_INT") (class "Default")
      (node (ref "Q3") (pin "2") (pinfunction "S_2") (pintype "bidirectional"))
      (node (ref "R46") (pin "1") (pinfunction "1_1") (pintype "passive"))
      (node (ref "U4") (pin "F14") (pinfunction "P6_0_F14") (pintype "bidirectional"))
    )
    (net (code "59") (name "/LED_G") (class "Default")
      (node (ref "Q2") (pin "3") (pinfunction "D_3") (pintype "bidirectional"))
      (node (ref "R42") (pin "1") (pinfunction "1_1") (pintype "passive"))
    )
    (net (code "60") (name "/LED_G_D") (class "Default")
      (node (ref "D3") (pin "2") (pinfunction "GREEN_2") (pintype "passive"))
      (node (ref "R42") (pin "2") (pinfunction "2_2") (pintype "passive"))
    )
    (net (code "61") (name "/LED_G_INT") (class "Default")
      (node (ref "Q2") (pin "2") (pinfunction "S_2") (pintype "bidirectional"))
      (node (ref "R45") (pin "1") (pinfunction "1_1") (pintype "passive"))
      (node (ref "U4") (pin "G27") (pinfunction "P14_1_G27") (pintype "bidirectional"))
    )
    (net (code "62") (name "/LED_R") (class "Default")
      (node (ref "Q1") (pin "3") (pinfunction "D_3") (pintype "bidirectional"))
      (node (ref "R43") (pin "1") (pinfunction "1_1") (pintype "passive"))
    )
    (net (code "63") (name "/LED_R_D") (class "Default")
      (node (ref "D3") (pin "3") (pinfunction "RED_3") (pintype "passive"))
      (node (ref "R43") (pin "2") (pinfunction "2_2") (pintype "passive"))
    )
    (net (code "64") (name "/LED_R_INT") (class "Default")
      (node (ref "Q1") (pin "2") (pinfunction "S_2") (pintype "bidirectional"))
      (node (ref "R44") (pin "1") (pinfunction "1_1") (pintype "passive"))
      (node (ref "U4") (pin "L7") (pinfunction "P0_0_L7") (pintype "bidirectional"))
    )
    (net (code "65") (name "/LFXO_N") (class "Default")
      (node (ref "C35") (pin "1") (pinfunction "1_1") (pintype "passive"))
      (node (ref "U4") (pin "P6") (pinfunction "LFXO_N_P6") (pintype "input"))
      (node (ref "Y2") (pin "1") (pinfunction "1_1") (pintype "passive"))
    )
    (net (code "66") (name "/LFXO_P") (class "Default")
      (node (ref "C34") (pin "1") (pinfunction "1_1") (pintype "passive"))
      (node (ref "U4") (pin "R5") (pinfunction "LFXO_P_R5") (pintype "input"))
      (node (ref "Y2") (pin "2") (pinfunction "2_2") (pintype "passive"))
    )
    (net (code "67") (name "/MIPI_R") (class "Default")
      (node (ref "R39") (pin "2") (pinfunction "2_2") (pintype "passive"))
      (node (ref "U4") (pin "J13") (pinfunction "MIPI_REXT_J13") (pintype "passive"))
    )
    (net (code "68") (name "/P0") (class "Default")
      (node (ref "B4") (pin "7") (pinfunction "CH6_7") (pintype "passive"))
      (node (ref "J4") (pin "6") (pinfunction "6_6") (pintype "passive"))
      (node (ref "U4") (pin "M22") (pinfunction "P7_4_FLEX_M22") (pintype "bidirectional"))
    )
    (net (code "69") (name "/P1") (class "Default")
      (node (ref "B4") (pin "6") (pinfunction "CH5_6") (pintype "passive"))
      (node (ref "J4") (pin "5") (pinfunction "5_5") (pintype "passive"))
      (node (ref "U4") (pin "L19") (pinfunction "P7_5_FLEX_L19") (pintype "bidirectional"))
    )
    (net (code "70") (name "/P2") (class "Default")
      (node (ref "B4") (pin "5") (pinfunction "CH4_5") (pintype "passive"))
      (node (ref "J4") (pin "4") (pinfunction "4_4") (pintype "passive"))
      (node (ref "U4") (pin "N27") (pinfunction "P7_6_FLEX_N27") (pintype "bidirectional"))
    )
    (net (code "71") (name "/P3") (class "Default")
      (node (ref "B4") (pin "4") (pinfunction "CH3_4") (pintype "passive"))
      (node (ref "J4") (pin "3") (pinfunction "3_3") (pintype "passive"))
      (node (ref "U4") (pin "N25") (pinfunction "P7_7_FLEX_N25") (pintype "bidirectional"))
    )
    (net (code "72") (name "/QWIIC_SCL") (class "Default")
      (node (ref "B6") (pin "8") (pinfunction "B1_8") (pintype "passive"))
      (node (ref "D1") (pin "4") (pinfunction "CATHODE3_4") (pintype "passive"))
      (node (ref "J1") (pin "4") (pinfunction "4_4") (pintype "passive"))
    )
    (net (code "73") (name "/QWIIC_SCL_INT") (class "Default")
      (node (ref "B6") (pin "5") (pinfunction "A1_5") (pintype "passive"))
      (node (ref "U4") (pin "K6") (pinfunction "P0_5_K6") (pintype "bidirectional"))
    )
    (net (code "74") (name "/QWIIC_SDA") (class "Default")
      (node (ref "B6") (pin "1") (pinfunction "B2_1") (pintype "passive"))
      (node (ref "D1") (pin "5") (pinfunction "CATHODE4_5") (pintype "passive"))
      (node (ref "J1") (pin "3") (pinfunction "3_3") (pintype "passive"))
    )
    (net (code "75") (name "/QWIIC_SDA_INT") (class "Default")
      (node (ref "B6") (pin "4") (pinfunction "A2_4") (pintype "passive"))
      (node (ref "U4") (pin "K8") (pinfunction "P0_4_K8") (pintype "bidirectional"))
    )
    (net (code "76") (name "/RECOVERY_MODE") (class "Default")
      (node (ref "D1") (pin "3") (pinfunction "CATHODE2_3") (pintype "passive"))
    )
    (net (code "77") (name "/RST_N") (class "Default")
      (node (ref "C37") (pin "2") (pinfunction "2_2") (pintype "passive"))
      (node (ref "Q4") (pin "2") (pinfunction "S_2") (pintype "bidirectional"))
      (node (ref "R36") (pin "1") (pinfunction "1_1") (pintype "passive"))
      (node (ref "U4") (pin "D6") (pinfunction "NSRST_D6") (pintype "input"))
    )
    (net (code "78") (name "/RST_N_EXT") (class "Default")
      (node (ref "B4") (pin "1") (pinfunction "CH1_1") (pintype "passive"))
      (node (ref "J4") (pin "7") (pinfunction "7_7") (pintype "passive"))
      (node (ref "Q4") (pin "3") (pinfunction "D_3") (pintype "bidirectional"))
      (node (ref "R54") (pin "1") (pinfunction "1_1") (pintype "passive"))
    )
    (net (code "79") (name "/SEUART_RX_INT") (class "Default")
      (node (ref "R34") (pin "1") (pinfunction "1_1") (pintype "passive"))
      (node (ref "U4") (pin "B2") (pinfunction "SEUART_RX_B2") (pintype "input"))
    )
    (net (code "80") (name "/SEUART_TX_INT") (class "Default")
      (node (ref "R35") (pin "1") (pinfunction "1_1") (pintype "passive"))
      (node (ref "U4") (pin "C5") (pinfunction "SEUART_TX_C5") (pintype "output"))
    )
    (net (code "81") (name "/TOF_I2C_GPIO") (class "Default")
      (node (ref "U4") (pin "J25") (pinfunction "P9_3_J25") (pintype "bidirectional"))
    )
    (net (code "82") (name "/TOF_I2C_INT") (class "Default")
      (node (ref "U4") (pin "L17") (pinfunction "P15_6_L17") (pintype "bidirectional"))
    )
    (net (code "83") (name "/TOF_I2C_LPN") (class "Default")
      (node (ref "U4") (pin "G25") (pinfunction "P14_2_G25") (pintype "bidirectional"))
    )
    (net (code "84") (name "/TOF_I2C_RST") (class "Default")
      (node (ref "U4") (pin "J23") (pinfunction "P9_4_J23") (pintype "bidirectional"))
    )
    (net (code "85") (name "/TOF_I2C_SCL") (class "Default")
      (node (ref "U4") (pin "L3") (pinfunction "P1_1_L3") (pintype "bidirectional"))
    )
    (net (code "86") (name "/TOF_I2C_SDA") (class "Default")
      (node (ref "U4") (pin "L1") (pinfunction "P1_0_L1") (pintype "bidirectional"))
    )
    (net (code "87") (name "/USB_D_N") (class "Default")
      (node (ref "U4") (pin "N15") (pinfunction "USB_DM_N15") (pintype "bidirectional"))
    )
    (net (code "88") (name "/USB_D_P") (class "Default")
      (node (ref "U4") (pin "R15") (pinfunction "USB_DP_R15") (pintype "bidirectional"))
    )
    (net (code "89") (name "/USB_D_SEL") (class "Default")
      (node (ref "U4") (pin "K18") (pinfunction "P15_0_FLEX_K18") (pintype "bidirectional"))
    )
    (net (code "90") (name "/USB_D_SEL_FB") (class "Default")
      (node (ref "U4") (pin "N23") (pinfunction "P15_1_FLEX_N23") (pintype "bidirectional"))
    )
    (net (code "91") (name "/USB_R") (class "Default")
      (node (ref "R38") (pin "1") (pinfunction "1_1") (pintype "passive"))
      (node (ref "U4") (pin "K14") (pinfunction "USB_REXT_K14") (pintype "passive"))
    )
    (net (code "92") (name "/USR_SW") (class "Default")
      (node (ref "B7") (pin "4") (pinfunction "CH3_4") (pintype "passive"))
      (node (ref "R52") (pin "2") (pinfunction "2_2") (pintype "passive"))
      (node (ref "R53") (pin "2") (pinfunction "2_2") (pintype "passive"))
      (node (ref "S2") (pin "1") (pinfunction "NO_1") (pintype "passive"))
      (node (ref "S2") (pin "5") (pinfunction "NO_5") (pintype "passive"))
    )
    (net (code "93") (name "/USR_SW_INT") (class "Default")
      (node (ref "C119") (pin "1") (pinfunction "1_1") (pintype "passive"))
      (node (ref "R53") (pin "1") (pinfunction "1_1") (pintype "passive"))
      (node (ref "U4") (pin "M18") (pinfunction "P15_7_M18") (pintype "bidirectional"))
    )
    (net (code "94") (name "/VREF_P") (class "Default")
      (node (ref "C112") (pin "2") (pinfunction "2_2") (pintype "passive"))
      (node (ref "U4") (pin "M4") (pinfunction "VREF_P_M4") (pintype "passive"))
    )
    (net (code "95") (name "/VREG_AON") (class "Default")
      (node (ref "R48") (pin "2") (pinfunction "2_2") (pintype "passive"))
      (node (ref "U4") (pin "L11") (pinfunction "VREG_AON_L11") (pintype "power_in"))
    )
    (net (code "96") (name "/VREG_AON_INT") (class "Default")
      (node (ref "C113") (pin "2") (pinfunction "2_2") (pintype "passive"))
      (node (ref "R48") (pin "1") (pinfunction "1_1") (pintype "passive"))
    )
    (net (code "97") (name "/VREG_DIG_1V8") (class "Default")
      (node (ref "R47") (pin "1") (pinfunction "1_1") (pintype "passive"))
      (node (ref "U4") (pin "J11") (pinfunction "VREG_DIG_1V8_J11") (pintype "power_in"))
    )
    (net (code "98") (name "/VREG_DIG_1V8_INT") (class "Default")
      (node (ref "C115") (pin "2") (pinfunction "2_2") (pintype "passive"))
      (node (ref "R47") (pin "2") (pinfunction "2_2") (pintype "passive"))
    )
    (net (code "99") (name "/VREG_LP_1V8") (class "Default")
      (node (ref "C114") (pin "2") (pinfunction "2_2") (pintype "passive"))
      (node (ref "U4") (pin "N5") (pinfunction "VREG_LP_1V8_N5") (pintype "power_in"))
    )
    (net (code "100") (name "/VREG_MIPI_0V8") (class "Default")
      (node (ref "C118") (pin "2") (pinfunction "2_2") (pintype "passive"))
      (node (ref "U4") (pin "L13") (pinfunction "VREG_MIPI_0V8_L13") (pintype "power_in"))
    )
    (net (code "101") (name "/VREG_MIPI_1V8") (class "Default")
      (node (ref "C116") (pin "2") (pinfunction "2_2") (pintype "passive"))
      (node (ref "C117") (pin "2") (pinfunction "2_2") (pintype "passive"))
      (node (ref "U4") (pin "G13") (pinfunction "VREG_MIPI_1V8_G13") (pintype "power_in"))
      (node (ref "U4") (pin "M12") (pinfunction "VDD_MIPI_1V8_M12") (pintype "power_in"))
    )
    (net (code "102") (name "/VSW") (class "Default")
      (node (ref "L1") (pin "1") (pinfunction "1_1") (pintype "passive"))
      (node (ref "U4") (pin "P4") (pinfunction "VSW_P4") (pintype "passive"))
      (node (ref "U4") (pin "R1") (pinfunction "VSW_R1") (pintype "passive"))
    )
    (net (code "103") (name "/WIFI_GPIO_1") (class "Default")
      (node (ref "U4") (pin "A5") (pinfunction "P13_5_A5") (pintype "bidirectional"))
    )
    (net (code "104") (name "/WIFI_GPIO_2") (class "Default")
      (node (ref "U4") (pin "A7") (pinfunction "P5_3_A7") (pintype "bidirectional"))
    )
    (net (code "105") (name "/WIFI_I2S_SCLK") (class "Default")
      (node (ref "U4") (pin "C1") (pinfunction "P12_2_C1") (pintype "bidirectional"))
    )
    (net (code "106") (name "/WIFI_I2S_SDI") (class "Default")
      (node (ref "U4") (pin "D2") (pinfunction "P12_0_D2") (pintype "bidirectional"))
    )
    (net (code "107") (name "/WIFI_I2S_SDO") (class "Default")
      (node (ref "U4") (pin "D4") (pinfunction "P12_1_D4") (pintype "bidirectional"))
    )
    (net (code "108") (name "/WIFI_I2S_WS") (class "Default")
      (node (ref "U4") (pin "E7") (pinfunction "P12_3_E7") (pintype "bidirectional"))
    )
    (net (code "109") (name "/WIFI_IRQ") (class "Default")
      (node (ref "U4") (pin "K28") (pinfunction "P9_6_K28") (pintype "bidirectional"))
    )
    (net (code "110") (name "/WIFI_MISO") (class "Default")
      (node (ref "U4") (pin "A15") (pinfunction "P12_4_A15") (pintype "bidirectional"))
    )
    (net (code "111") (name "/WIFI_MOSI") (class "Default")
      (node (ref "U4") (pin "B16") (pinfunction "P12_5_B16") (pintype "bidirectional"))
    )
    (net (code "112") (name "/WIFI_SCLK") (class "Default")
      (node (ref "U4") (pin "F16") (pinfunction "P12_6_F16") (pintype "bidirectional"))
    )
    (net (code "113") (name "/WIFI_SSEL") (class "Default")
      (node (ref "U4") (pin "E17") (pinfunction "P12_7_E17") (pintype "bidirectional"))
    )
    (net (code "114") (name "/WL_H_WAKE") (class "Default")
      (node (ref "U4") (pin "M28") (pinfunction "P11_0_M28") (pintype "bidirectional"))
    )
    (net (code "115") (name "/WL_REG_ON") (class "Default")
      (node (ref "U4") (pin "L27") (pinfunction "P10_4_L27") (pintype "bidirectional"))
    )
    (net (code "116") (name "GND") (class "Default")
      (node (ref "B4") (pin "2") (pinfunction "GND_2") (pintype "passive"))
      (node (ref "B6") (pin "2") (pinfunction "GND_2") (pintype "passive"))
      (node (ref "B7") (pin "2") (pinfunction "GND_2") (pintype "passive"))
      (node (ref "C100") (pin "1") (pinfunction "1_1") (pintype "passive"))
      (node (ref "C101") (pin "1") (pinfunction "1_1") (pintype "passive"))
      (node (ref "C102") (pin "2") (pinfunction "2_2") (pintype "passive"))
      (node (ref "C103") (pin "1") (pinfunction "1_1") (pintype "passive"))
      (node (ref "C104") (pin "1") (pinfunction "1_1") (pintype "passive"))
      (node (ref "C105") (pin "2") (pinfunction "2_2") (pintype "passive"))
      (node (ref "C106") (pin "1") (pinfunction "1_1") (pintype "passive"))
      (node (ref "C107") (pin "1") (pinfunction "1_1") (pintype "passive"))
      (node (ref "C108") (pin "1") (pinfunction "1_1") (pintype "passive"))
      (node (ref "C109") (pin "2") (pinfunction "2_2") (pintype "passive"))
      (node (ref "C110") (pin "2") (pinfunction "2_2") (pintype "passive"))
      (node (ref "C111") (pin "1") (pinfunction "1_1") (pintype "passive"))
      (node (ref "C112") (pin "1") (pinfunction "1_1") (pintype "passive"))
      (node (ref "C113") (pin "1") (pinfunction "1_1") (pintype "passive"))
      (node (ref "C114") (pin "1") (pinfunction "1_1") (pintype "passive"))
      (node (ref "C115") (pin "1") (pinfunction "1_1") (pintype "passive"))
      (node (ref "C116") (pin "1") (pinfunction "1_1") (pintype "passive"))
      (node (ref "C117") (pin "1") (pinfunction "1_1") (pintype "passive"))
      (node (ref "C118") (pin "1") (pinfunction "1_1") (pintype "passive"))
      (node (ref "C119") (pin "2") (pinfunction "2_2") (pintype "passive"))
      (node (ref "C20") (pin "1") (pinfunction "1_1") (pintype "passive"))
      (node (ref "C22") (pin "1") (pinfunction "1_1") (pintype "passive"))
      (node (ref "C34") (pin "2") (pinfunction "2_2") (pintype "passive"))
      (node (ref "C35") (pin "2") (pinfunction "2_2") (pintype "passive"))
      (node (ref "C37") (pin "1") (pinfunction "1_1") (pintype "passive"))
      (node (ref "C38") (pin "1") (pinfunction "1_1") (pintype "passive"))
      (node (ref "C84") (pin "1") (pinfunction "1_1") (pintype "passive"))
      (node (ref "C85") (pin "1") (pinfunction "1_1") (pintype "passive"))
      (node (ref "C86") (pin "2") (pinfunction "2_2") (pintype "passive"))
      (node (ref "C87") (pin "2") (pinfunction "2_2") (pintype "passive"))
      (node (ref "C88") (pin "1") (pinfunction "1_1") (pintype "passive"))
      (node (ref "C89") (pin "2") (pinfunction "2_2") (pintype "passive"))
      (node (ref "C90") (pin "1") (pinfunction "1_1") (pintype "passive"))
      (node (ref "C91") (pin "1") (pinfunction "1_1") (pintype "passive"))
      (node (ref "C92") (pin "2") (pinfunction "2_2") (pintype "passive"))
      (node (ref "C93") (pin "1") (pinfunction "1_1") (pintype "passive"))
      (node (ref "C94") (pin "1") (pinfunction "1_1") (pintype "passive"))
      (node (ref "C95") (pin "2") (pinfunction "2_2") (pintype "passive"))
      (node (ref "C96") (pin "1") (pinfunction "1_1") (pintype "passive"))
      (node (ref "C97") (pin "1") (pinfunction "1_1") (pintype "passive"))
      (node (ref "C98") (pin "1") (pinfunction "1_1") (pintype "passive"))
      (node (ref "C99") (pin "1") (pinfunction "1_1") (pintype "passive"))
      (node (ref "D1") (pin "2") (pinfunction "ANODE_2") (pintype "passive"))
      (node (ref "J1") (pin "1") (pinfunction "1_1") (pintype "passive"))
      (node (ref "J1") (pin "S1") (pinfunction "SHIELD_S1") (pintype "passive"))
      (node (ref "J1") (pin "S2") (pinfunction "SHIELD_S2") (pintype "passive"))
      (node (ref "J4") (pin "1") (pinfunction "1_1") (pintype "passive"))
      (node (ref "J5") (pin "5") (pintype "passive"))
      (node (ref "R38") (pin "2") (pinfunction "2_2") (pintype "passive"))
      (node (ref "R39") (pin "1") (pinfunction "1_1") (pintype "passive"))
      (node (ref "R51") (pin "1") (pinfunction "1_1") (pintype "passive"))
      (node (ref "S2") (pin "2") (pinfunction "COM_2") (pintype "passive"))
      (node (ref "S2") (pin "3") (pinfunction "COM_3") (pintype "passive"))
      (node (ref "S2") (pin "4") (pinfunction "COM_4") (pintype "passive"))
      (node (ref "U4") (pin "B12") (pinfunction "VSS_B12") (pintype "power_in"))
      (node (ref "U4") (pin "B22") (pinfunction "VSS_B22") (pintype "power_in"))
      (node (ref "U4") (pin "B24") (pinfunction "VSS_B24") (pintype "power_in"))
      (node (ref "U4") (pin "C3") (pinfunction "RESERVED_C3") (pintype "input"))
      (node (ref "U4") (pin "D22") (pinfunction "VSS_D22") (pintype "power_in"))
      (node (ref "U4") (pin "E25") (pinfunction "VSS_E25") (pintype "power_in"))
      (node (ref "U4") (pin "E27") (pinfunction "VSS_E27") (pintype "power_in"))
      (node (ref "U4") (pin "F26") (pinfunction "VSS_F26") (pintype "power_in"))
      (node (ref "U4") (pin "G1") (pinfunction "VSS_G1") (pintype "power_in"))
      (node (ref "U4") (pin "H26") (pinfunction "VSS_H26") (pintype "power_in"))
      (node (ref "U4") (pin "L9") (pinfunction "VSS_L9") (pintype "power_in"))
      (node (ref "U4") (pin "M2") (pinfunction "VREF_N_M2") (pintype "passive"))
      (node (ref "U4") (pin "M20") (pinfunction "VSS_M20") (pintype "power_in"))
      (node (ref "U4") (pin "N1") (pinfunction "VSS_ANA_N1") (pintype "power_in"))
      (node (ref "U4") (pin "R13") (pinfunction "VSS_R13") (pintype "power_in"))
      (node (ref "U4") (pin "R25") (pinfunction "VSS_R25") (pintype "power_in"))
      (node (ref "U4") (pin "R3") (pinfunction "VSS_BUCK_R3") (pintype "power_in"))
      (node (ref "U4") (pin "R9") (pinfunction "VSS_R9") (pintype "power_in"))
      (node (ref "X1") (pin "2") (pinfunction "NO_CONNECT_1_2") (pintype "passive"))
      (node (ref "X1") (pin "4") (pinfunction "NO_CONNECT_2_4") (pintype "passive"))
    )
    (net (code "117") (name "VBUS") (class "Default")
      (node (ref "U4") (pin "H14") (pinfunction "USB_VBUS_H14") (pintype "input"))
    )
    (net (code "118") (name "VCC_1.8V") (class "Default")
      (node (ref "B6") (pin "3") (pinfunction "VCC(A)_3") (pintype "passive"))
      (node (ref "B6") (pin "6") (pinfunction "OE_6") (pintype "passive"))
      (node (ref "B7") (pin "5") (pinfunction "CH4_5") (pintype "passive"))
      (node (ref "C104") (pin "2") (pinfunction "2_2") (pintype "passive"))
      (node (ref "C105") (pin "1") (pinfunction "1_1") (pintype "passive"))
      (node (ref "C106") (pin "2") (pinfunction "2_2") (pintype "passive"))
      (node (ref "C107") (pin "2") (pinfunction "2_2") (pintype "passive"))
      (node (ref "C108") (pin "2") (pinfunction "2_2") (pintype "passive"))
      (node (ref "C84") (pin "2") (pinfunction "2_2") (pintype "passive"))
      (node (ref "J5") (pin "1") (pintype "passive"))
      (node (ref "Q1") (pin "1") (pinfunction "G_1") (pintype "bidirectional"))
      (node (ref "Q2") (pin "1") (pinfunction "G_1") (pintype "bidirectional"))
      (node (ref "Q3") (pin "1") (pinfunction "G_1") (pintype "bidirectional"))
      (node (ref "Q4") (pin "1") (pinfunction "G_1") (pintype "bidirectional"))
      (node (ref "R34") (pin "2") (pinfunction "2_2") (pintype "passive"))
      (node (ref "R35") (pin "2") (pinfunction "2_2") (pintype "passive"))
      (node (ref "R36") (pin "2") (pinfunction "2_2") (pintype "passive"))
      (node (ref "R37") (pin "2") (pinfunction "2_2") (pintype "passive"))
      (node (ref "R44") (pin "2") (pinfunction "2_2") (pintype "passive"))
      (node (ref "R45") (pin "2") (pinfunction "2_2") (pintype "passive"))
      (node (ref "R46") (pin "2") (pinfunction "2_2") (pintype "passive"))
      (node (ref "R49") (pin "2") (pinfunction "2_2") (pintype "passive"))
      (node (ref "R50") (pin "2") (pinfunction "2_2") (pintype "passive"))
      (node (ref "R52") (pin "1") (pinfunction "1_1") (pintype "passive"))
      (node (ref "U4") (pin "C13") (pinfunction "VDD_IO_1V8_C13") (pintype "power_in"))
      (node (ref "U4") (pin "F4") (pinfunction "VDD_IO_1V8_F4") (pintype "power_in"))
      (node (ref "U4") (pin "P24") (pinfunction "VDD_IO_1V8_P24") (pintype "power_in"))
    )
    (net (code "119") (name "VCC_3.3V") (class "Default")
      (node (ref "B4") (pin "3") (pinfunction "CH2_3") (pintype "passive"))
      (node (ref "B6") (pin "7") (pinfunction "VCC(B)_7") (pintype "passive"))
      (node (ref "C102") (pin "1") (pinfunction "1_1") (pintype "passive"))
      (node (ref "C103") (pin "2") (pinfunction "2_2") (pintype "passive"))
      (node (ref "C110") (pin "1") (pinfunction "1_1") (pintype "passive"))
      (node (ref "C111") (pin "2") (pinfunction "2_2") (pintype "passive"))
      (node (ref "C85") (pin "2") (pinfunction "2_2") (pintype "passive"))
      (node (ref "C88") (pin "2") (pinfunction "2_2") (pintype "passive"))
      (node (ref "C89") (pin "1") (pinfunction "1_1") (pintype "passive"))
      (node (ref "C90") (pin "2") (pinfunction "2_2") (pintype "passive"))
      (node (ref "C91") (pin "2") (pinfunction "2_2") (pintype "passive"))
      (node (ref "C92") (pin "1") (pinfunction "1_1") (pintype "passive"))
      (node (ref "C93") (pin "2") (pinfunction "2_2") (pintype "passive"))
      (node (ref "C94") (pin "2") (pinfunction "2_2") (pintype "passive"))
      (node (ref "C95") (pin "1") (pinfunction "1_1") (pintype "passive"))
      (node (ref "C96") (pin "2") (pinfunction "2_2") (pintype "passive"))
      (node (ref "D1") (pin "1") (pinfunction "CATHODE_1_1") (pintype "passive"))
      (node (ref "D3") (pin "4") (pinfunction "ANODE_4") (pintype "passive"))
      (node (ref "J1") (pin "2") (pinfunction "2_2") (pintype "passive"))
      (node (ref "J4") (pin "2") (pinfunction "2_2") (pintype "passive"))
      (node (ref "R54") (pin "2") (pinfunction "2_2") (pintype "passive"))
      (node (ref "U4") (pin "K12") (pinfunction "VDD_BATT_K12") (pintype "power_in"))
      (node (ref "U4") (pin "L5") (pinfunction "VDD_MAIN_L5") (pintype "power_in"))
      (node (ref "U4") (pin "P14") (pinfunction "VDD_USB_3V3_P14") (pintype "power_in"))
      (node (ref "U4") (pin "P2") (pinfunction "VDD_BUCK_P2") (pintype "power_in"))
      (node (ref "U4") (pin "P28") (pinfunction "VDD_IO_FLEX_P28") (pintype "power_in"))
    )
    (net (code "120") (name "VDD_CORE") (class "Default")
      (node (ref "C100") (pin "2") (pinfunction "2_2") (pintype "passive"))
      (node (ref "C101") (pin "2") (pinfunction "2_2") (pintype "passive"))
      (node (ref "C109") (pin "1") (pinfunction "1_1") (pintype "passive"))
      (node (ref "C86") (pin "1") (pinfunction "1_1") (pintype "passive"))
      (node (ref "C87") (pin "1") (pinfunction "1_1") (pintype "passive"))
      (node (ref "C97") (pin "2") (pinfunction "2_2") (pintype "passive"))
      (node (ref "C98") (pin "2") (pinfunction "2_2") (pintype "passive"))
      (node (ref "C99") (pin "2") (pinfunction "2_2") (pintype "passive"))
      (node (ref "L1") (pin "2") (pinfunction "2_2") (pintype "passive"))
      (node (ref "U4") (pin "A13") (pinfunction "VDD_CORE_0V8_A13") (pintype "power_in"))
      (node (ref "U4") (pin "C21") (pinfunction "VDD_SX_0V8_C21") (pintype "power_in"))
      (node (ref "U4") (pin "C25") (pinfunction "VDD_PLL_0V8_C25") (pintype "power_in"))
      (node (ref "U4") (pin "G3") (pinfunction "VDD_CORE_0V8_G3") (pintype "power_in"))
      (node (ref "U4") (pin "H24") (pinfunction "VDD_CORE_0V8_H24") (pintype "power_in"))
      (node (ref "U4") (pin "M6") (pinfunction "VREG_CORE_0V8_M6") (pintype "power_in"))
      (node (ref "U4") (pin "N17") (pinfunction "VDD_CORE_0V8_N17") (pintype "power_in"))
    )
    (net (code "121") (name "unconnected-(U4A-nc-PadC15)") (class "Default")
      (node (ref "U4") (pin "C15") (pinfunction "nc_C15") (pintype "power_in+no_connect"))
    )
    (net (code "122") (name "unconnected-(U4A-nc-PadC23)") (class "Default")
      (node (ref "U4") (pin "C23") (pinfunction "nc_C23") (pintype "power_in+no_connect"))
    )
    (net (code "123") (name "unconnected-(U4A-nc-PadD26)") (class "Default")
      (node (ref "U4") (pin "D26") (pinfunction "nc_D26") (pintype "power_in+no_connect"))
    )
    (net (code "124") (name "unconnected-(U4A-nc-PadF24)") (class "Default")
      (node (ref "U4") (pin "F24") (pinfunction "nc_F24") (pintype "power_in+no_connect"))
    )
    (net (code "125") (name "unconnected-(U4B-AMUX_N-PadE21)") (class "Default")
      (node (ref "U4") (pin "E21") (pinfunction "AMUX_N_E21") (pintype "passive+no_connect"))
    )
    (net (code "126") (name "unconnected-(U4B-AMUX_P-PadE23)") (class "Default")
      (node (ref "U4") (pin "E23") (pinfunction "AMUX_P_E23") (pintype "passive+no_connect"))
    )
    (net (code "127") (name "unconnected-(U4B-AMUX_PMU-PadG11)") (class "Default")
      (node (ref "U4") (pin "G11") (pinfunction "AMUX_PMU_G11") (pintype "passive+no_connect"))
    )
    (net (code "128") (name "unconnected-(U4B-nc-PadB26)") (class "Default")
      (node (ref "U4") (pin "B26") (pinfunction "nc_B26") (pintype "input+no_connect"))
    )
    (net (code "129") (name "unconnected-(U4B-nc-PadB28)") (class "Default")
      (node (ref "U4") (pin "B28") (pinfunction "nc_B28") (pintype "input+no_connect"))
    )
    (net (code "130") (name "unconnected-(U4B-nc-PadC27)") (class "Default")
      (node (ref "U4") (pin "C27") (pinfunction "nc_C27") (pintype "input+no_connect"))
    )
    (net (code "131") (name "unconnected-(U4B-nc-PadD28)") (class "Default")
      (node (ref "U4") (pin "D28") (pinfunction "nc_D28") (pintype "output+no_connect"))
    )
    (net (code "132") (name "unconnected-(U4B-nc-PadF28)") (class "Default")
      (node (ref "U4") (pin "F28") (pinfunction "nc_F28") (pintype "output+no_connect"))
    )
    (net (code "133") (name "unconnected-(U4C-P0_1-PadH12)") (class "Default")
      (node (ref "U4") (pin "H12") (pinfunction "P0_1_H12") (pintype "bidirectional+no_connect"))
    )
    (net (code "134") (name "unconnected-(U4C-P0_2-PadJ9)") (class "Default")
      (node (ref "U4") (pin "J9") (pinfunction "P0_2_J9") (pintype "bidirectional+no_connect"))
    )
    (net (code "135") (name "unconnected-(U4C-P0_3-PadN3)") (class "Default")
      (node (ref "U4") (pin "N3") (pinfunction "P0_3_N3") (pintype "bidirectional+no_connect"))
    )
    (net (code "136") (name "unconnected-(U4C-P0_6-PadH10)") (class "Default")
      (node (ref "U4") (pin "H10") (pinfunction "P0_6_H10") (pintype "bidirectional+no_connect"))
    )
    (net (code "137") (name "unconnected-(U4C-P0_7-PadJ7)") (class "Default")
      (node (ref "U4") (pin "J7") (pinfunction "P0_7_J7") (pintype "bidirectional+no_connect"))
    )
    (net (code "138") (name "unconnected-(U4C-P1_2-PadH8)") (class "Default")
      (node (ref "U4") (pin "H8") (pinfunction "P1_2_H8") (pintype "bidirectional"))
    )
    (net (code "139") (name "unconnected-(U4C-P1_3-PadK4)") (class "Default")
      (node (ref "U4") (pin "K4") (pinfunction "P1_3_K4") (pintype "bidirectional"))
    )
    (net (code "140") (name "unconnected-(U4C-P3_6-PadP22)") (class "Default")
      (node (ref "U4") (pin "P22") (pinfunction "P3_6_P22") (pintype "bidirectional+no_connect"))
    )
    (net (code "141") (name "unconnected-(U4C-P3_7{slash}JTAG0_TRACECLK-PadR23)") (class "Default")
      (node (ref "U4") (pin "R23") (pinfunction "P3_7/JTAG0_TRACECLK_R23") (pintype "bidirectional+no_connect"))
    )
    (net (code "142") (name "unconnected-(U4C-P4_2{slash}JTAG0_TDATA2-PadE9)") (class "Default")
      (node (ref "U4") (pin "E9") (pinfunction "P4_2/JTAG0_TDATA2_E9") (pintype "bidirectional"))
    )
    (net (code "143") (name "unconnected-(U4C-P4_3{slash}JTAG0_TDATA3-PadD8)") (class "Default")
      (node (ref "U4") (pin "D8") (pinfunction "P4_3/JTAG0_TDATA3_D8") (pintype "bidirectional"))
    )
    (net (code "144") (name "unconnected-(U4C-P5_0-PadB6)") (class "Default")
      (node (ref "U4") (pin "B6") (pinfunction "P5_0_B6") (pintype "bidirectional+no_connect"))
    )
    (net (code "145") (name "unconnected-(U4C-P5_1-PadE13)") (class "Default")
      (node (ref "U4") (pin "E13") (pinfunction "P5_1_E13") (pintype "bidirectional+no_connect"))
    )
    (net (code "146") (name "unconnected-(U4C-P5_2-PadB8)") (class "Default")
      (node (ref "U4") (pin "B8") (pinfunction "P5_2_B8") (pintype "bidirectional+no_connect"))
    )
    (net (code "147") (name "unconnected-(U4C-P5_4-PadD12)") (class "Default")
      (node (ref "U4") (pin "D12") (pinfunction "P5_4_D12") (pintype "bidirectional+no_connect"))
    )
    (net (code "148") (name "unconnected-(U4C-P5_5-PadC11)") (class "Default")
      (node (ref "U4") (pin "C11") (pinfunction "P5_5_C11") (pintype "bidirectional+no_connect"))
    )
    (net (code "149") (name "unconnected-(U4C-P5_6-PadB10)") (class "Default")
      (node (ref "U4") (pin "B10") (pinfunction "P5_6_B10") (pintype "bidirectional+no_connect"))
    )
    (net (code "150") (name "unconnected-(U4C-P6_1-PadE15)") (class "Default")
      (node (ref "U4") (pin "E15") (pinfunction "P6_1_E15") (pintype "bidirectional+no_connect"))
    )
    (net (code "151") (name "unconnected-(U4C-P6_2-PadD14)") (class "Default")
      (node (ref "U4") (pin "D14") (pinfunction "P6_2_D14") (pintype "bidirectional"))
    )
    (net (code "152") (name "unconnected-(U4C-P6_3-PadA11)") (class "Default")
      (node (ref "U4") (pin "A11") (pinfunction "P6_3_A11") (pintype "bidirectional+no_connect"))
    )
    (net (code "153") (name "unconnected-(U4C-P6_4-PadB14)") (class "Default")
      (node (ref "U4") (pin "B14") (pinfunction "P6_4_B14") (pintype "bidirectional"))
    )
    (net (code "154") (name "unconnected-(U4C-P6_5-PadG15)") (class "Default")
      (node (ref "U4") (pin "G15") (pinfunction "P6_5_G15") (pintype "bidirectional+no_connect"))
    )
    (net (code "155") (name "unconnected-(U4C-P7_0-PadB18)") (class "Default")
      (node (ref "U4") (pin "B18") (pinfunction "P7_0_B18") (pintype "bidirectional+no_connect"))
    )
    (net (code "156") (name "unconnected-(U4C-P7_1-PadD18)") (class "Default")
      (node (ref "U4") (pin "D18") (pinfunction "P7_1_D18") (pintype "bidirectional+no_connect"))
    )
    (net (code "157") (name "unconnected-(U4C-P7_2-PadF18)") (class "Default")
      (node (ref "U4") (pin "F18") (pinfunction "P7_2_F18") (pintype "bidirectional+no_connect"))
    )
    (net (code "158") (name "unconnected-(U4C-P7_3-PadA19)") (class "Default")
      (node (ref "U4") (pin "A19") (pinfunction "P7_3_A19") (pintype "bidirectional+no_connect"))
    )
    (net (code "159") (name "unconnected-(U4C-P9_0-PadH18)") (class "Default")
      (node (ref "U4") (pin "H18") (pinfunction "P9_0_H18") (pintype "bidirectional+no_connect"))
    )
    (net (code "160") (name "unconnected-(U4C-P9_1-PadH16)") (class "Default")
      (node (ref "U4") (pin "H16") (pinfunction "P9_1_H16") (pintype "bidirectional+no_connect"))
    )
    (net (code "161") (name "unconnected-(U4C-P9_5-PadJ21)") (class "Default")
      (node (ref "U4") (pin "J21") (pinfunction "P9_5_J21") (pintype "bidirectional"))
    )
    (net (code "162") (name "unconnected-(U4C-P9_7-PadJ19)") (class "Default")
      (node (ref "U4") (pin "J19") (pinfunction "P9_7_J19") (pintype "bidirectional+no_connect"))
    )
    (net (code "163") (name "unconnected-(U4C-P10_5-PadL25)") (class "Default")
      (node (ref "U4") (pin "L25") (pinfunction "P10_5_L25") (pintype "bidirectional+no_connect"))
    )
    (net (code "164") (name "unconnected-(U4C-P10_6-PadL23)") (class "Default")
      (node (ref "U4") (pin "L23") (pinfunction "P10_6_L23") (pintype "bidirectional+no_connect"))
    )
    (net (code "165") (name "unconnected-(U4C-P10_7-PadL21)") (class "Default")
      (node (ref "U4") (pin "L21") (pinfunction "P10_7_L21") (pintype "bidirectional+no_connect"))
    )
    (net (code "166") (name "unconnected-(U4C-P11_1-PadJ17)") (class "Default")
      (node (ref "U4") (pin "J17") (pinfunction "P11_1_J17") (pintype "bidirectional+no_connect"))
    )
    (net (code "167") (name "unconnected-(U4C-P11_2-PadM26)") (class "Default")
      (node (ref "U4") (pin "M26") (pinfunction "P11_2_M26") (pintype "bidirectional+no_connect"))
    )
    (net (code "168") (name "unconnected-(U4C-P11_3-PadM24)") (class "Default")
      (node (ref "U4") (pin "M24") (pinfunction "P11_3_M24") (pintype "bidirectional+no_connect"))
    )
    (net (code "169") (name "unconnected-(U4C-P13_2-PadF8)") (class "Default")
      (node (ref "U4") (pin "F8") (pinfunction "P13_2_F8") (pintype "bidirectional"))
    )
    (net (code "170") (name "unconnected-(U4C-P14_0-PadA17)") (class "Default")
      (node (ref "U4") (pin "A17") (pinfunction "P14_0_A17") (pintype "bidirectional+no_connect"))
    )
    (net (code "171") (name "unconnected-(U4C-P14_3-PadP18)") (class "Default")
      (node (ref "U4") (pin "P18") (pinfunction "P14_3_P18") (pintype "bidirectional+no_connect"))
    )
    (net (code "172") (name "unconnected-(U4C-P14_4-PadR19)") (class "Default")
      (node (ref "U4") (pin "R19") (pinfunction "P14_4_R19") (pintype "bidirectional+no_connect"))
    )
    (net (code "173") (name "unconnected-(U4C-P14_5-PadM16)") (class "Default")
      (node (ref "U4") (pin "M16") (pinfunction "P14_5_M16") (pintype "bidirectional+no_connect"))
    )
    (net (code "174") (name "unconnected-(U4C-P14_6-PadL15)") (class "Default")
      (node (ref "U4") (pin "L15") (pinfunction "P14_6_L15") (pintype "bidirectional+no_connect"))
    )
    (net (code "175") (name "unconnected-(U4C-P14_7-PadR17)") (class "Default")
      (node (ref "U4") (pin "R17") (pinfunction "P14_7_R17") (pintype "bidirectional+no_connect"))
    )
    (net (code "176") (name "unconnected-(U4C-P15_2_FLEX-PadN21)") (class "Default")
      (node (ref "U4") (pin "N21") (pinfunction "P15_2_FLEX_N21") (pintype "bidirectional+no_connect"))
    )
    (net (code "177") (name "unconnected-(U4C-P15_3_FLEX-PadP26)") (class "Default")
      (node (ref "U4") (pin "P26") (pinfunction "P15_3_FLEX_P26") (pintype "bidirectional+no_connect"))
    )
    (net (code "178") (name "unconnected-(U4D-MIPICSI_0_N-PadR7)") (class "Default")
      (node (ref "U4") (pin "R7") (pinfunction "MIPICSI_0_N_R7") (pintype "bidirectional+no_connect"))
    )
    (net (code "179") (name "unconnected-(U4D-MIPICSI_0_P-PadP8)") (class "Default")
      (node (ref "U4") (pin "P8") (pinfunction "MIPICSI_0_P_P8") (pintype "bidirectional+no_connect"))
    )
    (net (code "180") (name "unconnected-(U4D-MIPICSI_1_N-PadN9)") (class "Default")
      (node (ref "U4") (pin "N9") (pinfunction "MIPICSI_1_N_N9") (pintype "bidirectional+no_connect"))
    )
    (net (code "181") (name "unconnected-(U4D-MIPICSI_1_P-PadM10)") (class "Default")
      (node (ref "U4") (pin "M10") (pinfunction "MIPICSI_1_P_M10") (pintype "bidirectional+no_connect"))
    )
    (net (code "182") (name "unconnected-(U4D-MIPICSI_C_N-PadN7)") (class "Default")
      (node (ref "U4") (pin "N7") (pinfunction "MIPICSI_C_N_N7") (pintype "output+no_connect"))
    )
    (net (code "183") (name "unconnected-(U4D-MIPICSI_C_P-PadM8)") (class "Default")
      (node (ref "U4") (pin "M8") (pinfunction "MIPICSI_C_P_M8") (pintype "output+no_connect"))
    )
    (net (code "184") (name "unconnected-(U4D-MIPIDSI_0_N-PadN11)") (class "Default")
      (node (ref "U4") (pin "N11") (pinfunction "MIPIDSI_0_N_N11") (pintype "bidirectional+no_connect"))
    )
    (net (code "185") (name "unconnected-(U4D-MIPIDSI_0_P-PadP10)") (class "Default")
      (node (ref "U4") (pin "P10") (pinfunction "MIPIDSI_0_P_P10") (pintype "bidirectional+no_connect"))
    )
    (net (code "186") (name "unconnected-(U4D-MIPIDSI_1_N-PadM14)") (class "Default")
      (node (ref "U4") (pin "M14") (pinfunction "MIPIDSI_1_N_M14") (pintype "bidirectional+no_connect"))
    )
    (net (code "187") (name "unconnected-(U4D-MIPIDSI_1_P-PadN13)") (class "Default")
      (node (ref "U4") (pin "N13") (pinfunction "MIPIDSI_1_P_N13") (pintype "bidirectional+no_connect"))
    )
    (net (code "188") (name "unconnected-(U4D-MIPIDSI_C_N-PadP12)") (class "Default")
      (node (ref "U4") (pin "P12") (pinfunction "MIPIDSI_C_N_P12") (pintype "output+no_connect"))
    )
    (net (code "189") (name "unconnected-(U4D-MIPIDSI_C_P-PadR11)") (class "Default")
      (node (ref "U4") (pin "R11") (pinfunction "MIPIDSI_C_P_R11") (pintype "output+no_connect"))
    )
    (net (code "190") (name "unconnected-(U4D-USB_IO_ID-PadP16)") (class "Default")
      (node (ref "U4") (pin "P16") (pinfunction "USB_IO_ID_P16") (pintype "input+no_connect"))
    )
  )
)
